# DIS08070H-V2_0-20231204.net
KiCad netlist of a schematic drawn in EAGLE
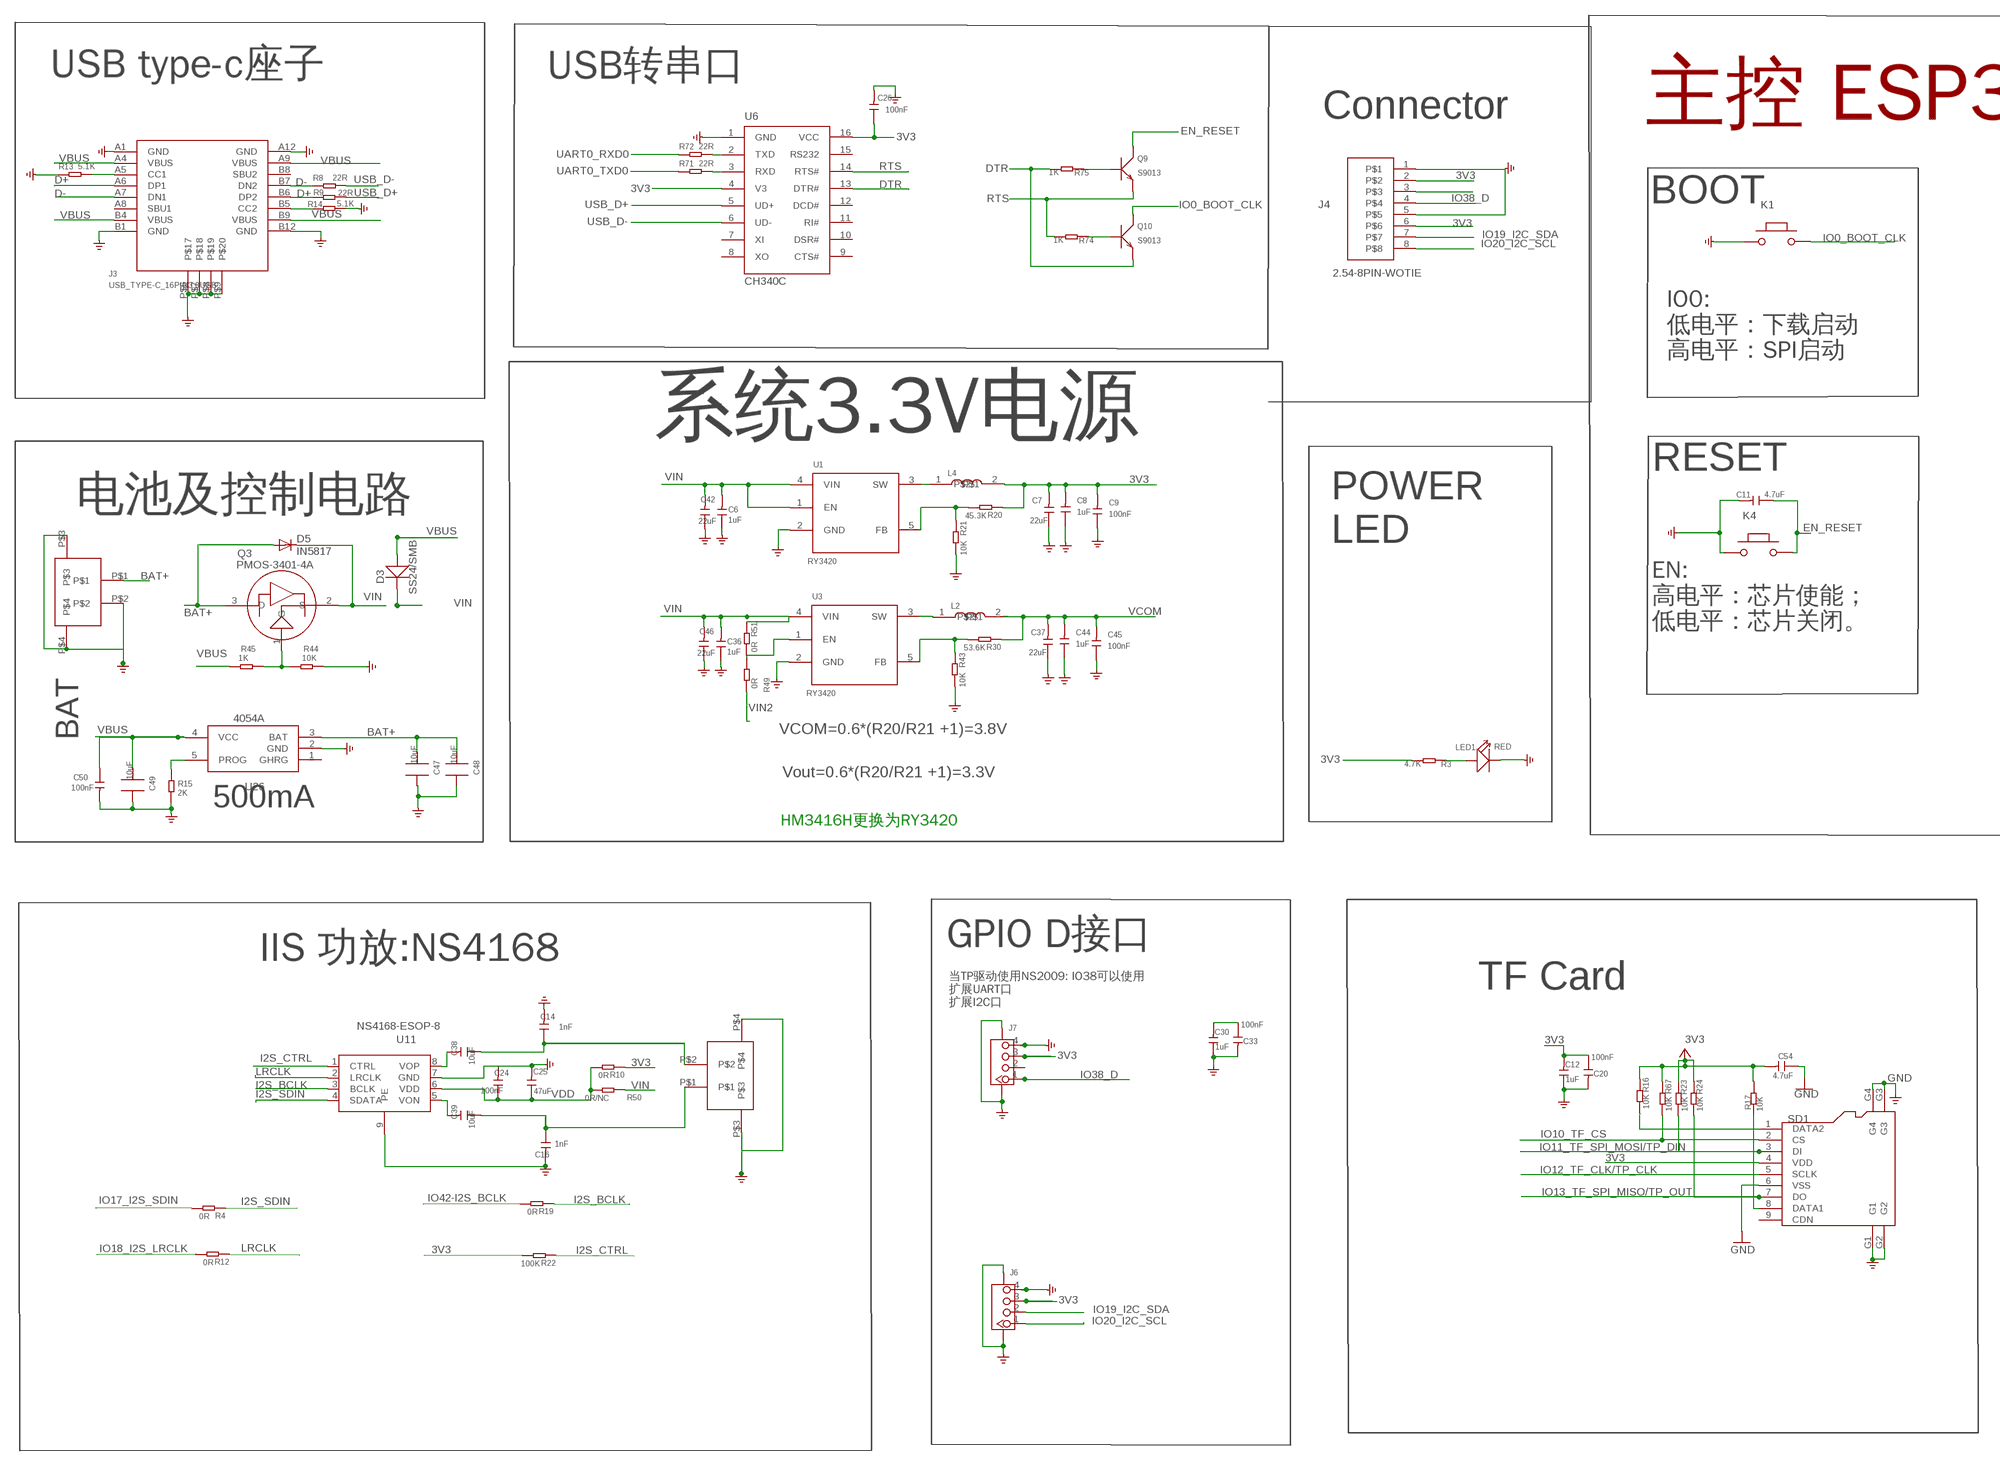
[diagram p0: schematic, sheet 1, part 1 of 2]
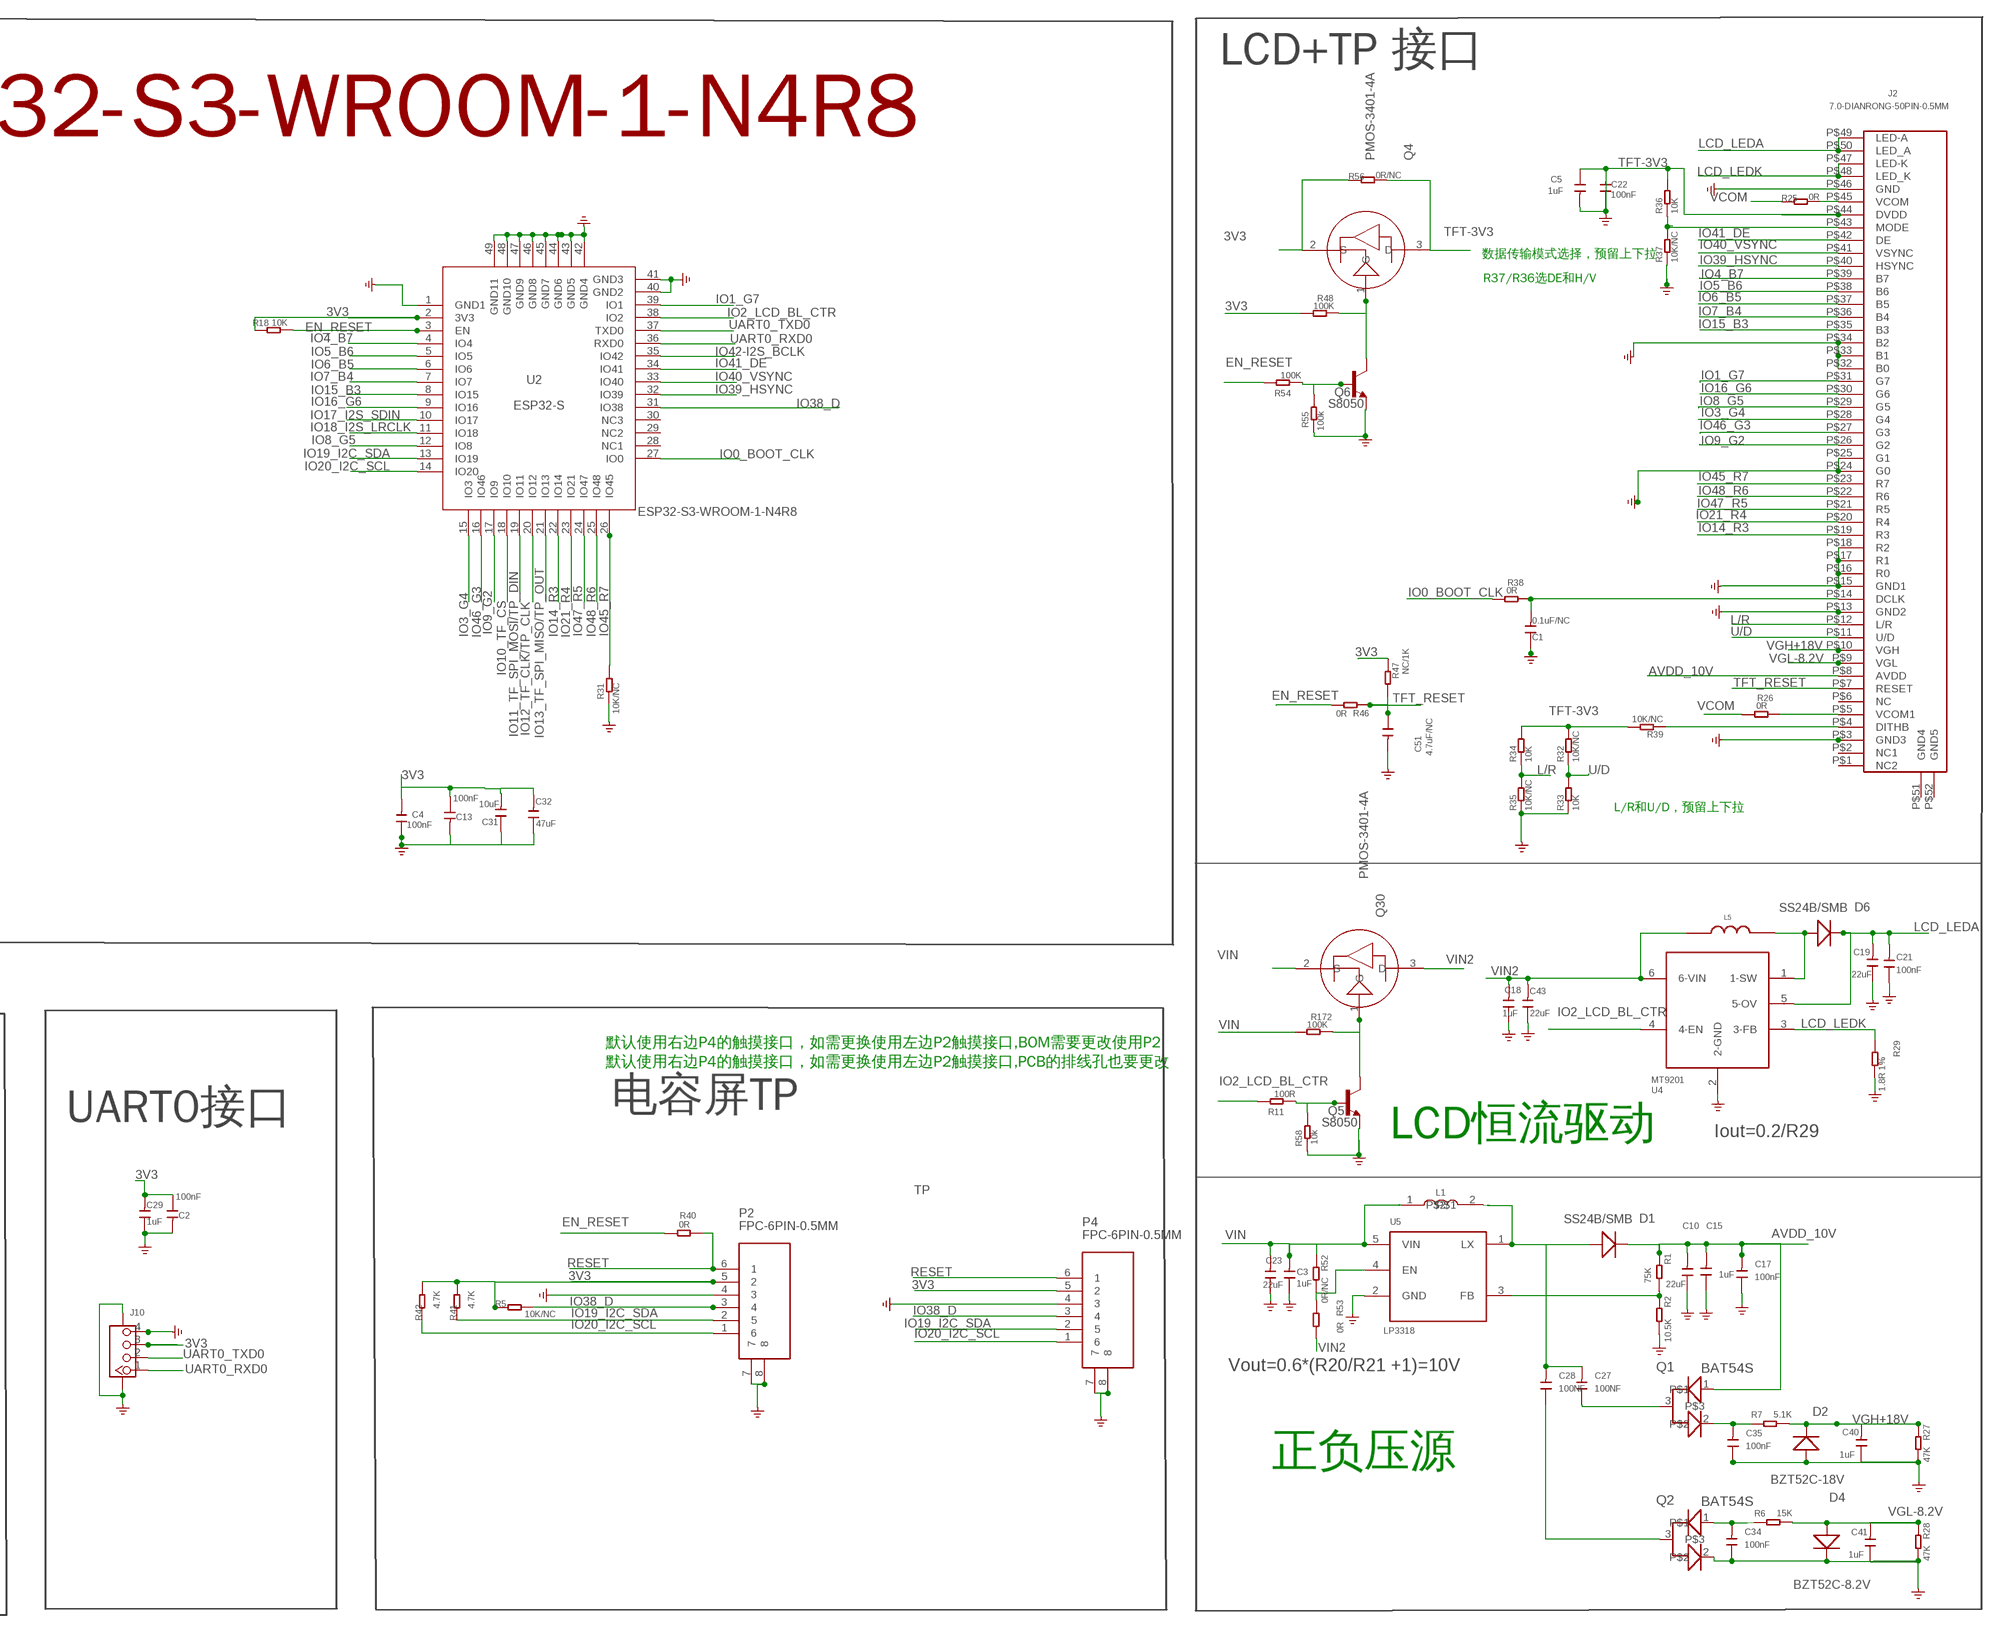
[diagram p1: schematic, sheet 1, part 2 of 2]

(export (version "E")
  (design (tool "Eeschema 10.0.6"))
  (components
    (comp (ref "C1")
      (value "0.1uF/NC")
      (footprint "eagle-import:DISCRETE_C0603")
      (libsource (lib "eagle-import") (part "DISCRETE_C-0603"))
    )
    (comp (ref "C2")
      (value "100nF")
      (footprint "eagle-import:C0603")
      (libsource (lib "eagle-import") (part "C-0603"))
    )
    (comp (ref "C3")
      (value "1uF")
      (footprint "eagle-import:0603")
      (libsource (lib "eagle-import") (part "C0603"))
    )
    (comp (ref "C4")
      (value "100nF")
      (footprint "eagle-import:C0603")
      (libsource (lib "eagle-import") (part "C-0603"))
    )
    (comp (ref "C5")
      (value "1uF")
      (footprint "eagle-import:C0603")
      (libsource (lib "eagle-import") (part "C-0603"))
    )
    (comp (ref "C6")
      (value "1uF")
      (footprint "eagle-import:0603")
      (libsource (lib "eagle-import") (part "C0603"))
    )
    (comp (ref "C7")
      (value "22uF")
      (footprint "eagle-import:0805")
      (libsource (lib "eagle-import") (part "C0805"))
    )
    (comp (ref "C8")
      (value "1uF")
      (footprint "eagle-import:0603")
      (libsource (lib "eagle-import") (part "C0603"))
    )
    (comp (ref "C9")
      (value "100nF")
      (footprint "eagle-import:0603")
      (libsource (lib "eagle-import") (part "C0603"))
    )
    (comp (ref "C10")
      (value "22uF")
      (footprint "eagle-import:0805")
      (libsource (lib "eagle-import") (part "C0805"))
    )
    (comp (ref "C11")
      (value "4.7uF")
      (footprint "eagle-import:0603")
      (libsource (lib "eagle-import") (part "C0603"))
    )
    (comp (ref "C12")
      (value "1uF")
      (footprint "eagle-import:DISCRETE_C0603")
      (libsource (lib "eagle-import") (part "A_xbj_DISCRETE_C-0603"))
    )
    (comp (ref "C13")
      (value "100nF")
      (footprint "eagle-import:C0603")
      (libsource (lib "eagle-import") (part "C-0603"))
    )
    (comp (ref "C14")
      (value "1nF")
      (footprint "eagle-import:C0603")
      (libsource (lib "eagle-import") (part "C-0603"))
    )
    (comp (ref "C15")
      (value "1uF")
      (footprint "eagle-import:0603")
      (libsource (lib "eagle-import") (part "C0603"))
    )
    (comp (ref "C16")
      (value "1nF")
      (footprint "eagle-import:C0603")
      (libsource (lib "eagle-import") (part "C-0603"))
    )
    (comp (ref "C17")
      (value "100nF")
      (footprint "eagle-import:0603")
      (libsource (lib "eagle-import") (part "C0603"))
    )
    (comp (ref "C18")
      (value "1uF")
      (footprint "eagle-import:0603")
      (libsource (lib "eagle-import") (part "C0603"))
    )
    (comp (ref "C19")
      (value "22uF")
      (footprint "eagle-import:0805")
      (libsource (lib "eagle-import") (part "C0805"))
    )
    (comp (ref "C20")
      (value "100nF")
      (footprint "eagle-import:C0603")
      (libsource (lib "eagle-import") (part "C-0603"))
    )
    (comp (ref "C21")
      (value "100nF")
      (footprint "eagle-import:0603")
      (libsource (lib "eagle-import") (part "C0603"))
    )
    (comp (ref "C22")
      (value "100nF")
      (footprint "eagle-import:C0603")
      (libsource (lib "eagle-import") (part "C-0603"))
    )
    (comp (ref "C23")
      (value "22uF")
      (footprint "eagle-import:0805")
      (libsource (lib "eagle-import") (part "C0805"))
    )
    (comp (ref "C24")
      (value "100nF")
      (footprint "eagle-import:C0603")
      (libsource (lib "eagle-import") (part "C-0603"))
    )
    (comp (ref "C25")
      (value "47uF")
      (footprint "eagle-import:0805")
      (libsource (lib "eagle-import") (part "C0805"))
    )
    (comp (ref "C26")
      (value "100nF")
      (footprint "eagle-import:0603")
      (libsource (lib "eagle-import") (part "C0603"))
    )
    (comp (ref "C27")
      (value "100NF")
      (footprint "eagle-import:0603")
      (libsource (lib "eagle-import") (part "C0603"))
    )
    (comp (ref "C28")
      (value "100NF")
      (footprint "eagle-import:0603")
      (libsource (lib "eagle-import") (part "C0603"))
    )
    (comp (ref "C29")
      (value "1uF")
      (footprint "eagle-import:DISCRETE_C0603")
      (libsource (lib "eagle-import") (part "A_xbj_DISCRETE_C-0603"))
    )
    (comp (ref "C30")
      (value "1uF")
      (footprint "eagle-import:DISCRETE_C0603")
      (libsource (lib "eagle-import") (part "A_xbj_DISCRETE_C-0603"))
    )
    (comp (ref "C31")
      (value "10uF")
      (footprint "eagle-import:DISCRETE_C0603")
      (libsource (lib "eagle-import") (part "DISCRETE_C-0603"))
    )
    (comp (ref "C32")
      (value "47uF")
      (footprint "eagle-import:0805")
      (libsource (lib "eagle-import") (part "C0805"))
    )
    (comp (ref "C33")
      (value "100nF")
      (footprint "eagle-import:C0603")
      (libsource (lib "eagle-import") (part "C-0603"))
    )
    (comp (ref "C34")
      (value "100nF")
      (footprint "eagle-import:0603")
      (libsource (lib "eagle-import") (part "C0603"))
    )
    (comp (ref "C35")
      (value "100nF")
      (footprint "eagle-import:0603")
      (libsource (lib "eagle-import") (part "C0603"))
    )
    (comp (ref "C36")
      (value "1uF")
      (footprint "eagle-import:0603")
      (libsource (lib "eagle-import") (part "C0603"))
    )
    (comp (ref "C37")
      (value "22uF")
      (footprint "eagle-import:0805")
      (libsource (lib "eagle-import") (part "C0805"))
    )
    (comp (ref "C38")
      (value "10uF")
      (footprint "eagle-import:C0603")
      (libsource (lib "eagle-import") (part "C-0603"))
    )
    (comp (ref "C39")
      (value "10uF")
      (footprint "eagle-import:C0603")
      (libsource (lib "eagle-import") (part "C-0603"))
    )
    (comp (ref "C40")
      (value "1uF")
      (footprint "eagle-import:0805")
      (libsource (lib "eagle-import") (part "C0805"))
    )
    (comp (ref "C41")
      (value "1uF")
      (footprint "eagle-import:0805")
      (libsource (lib "eagle-import") (part "C0805"))
    )
    (comp (ref "C42")
      (value "22uF")
      (footprint "eagle-import:0805")
      (libsource (lib "eagle-import") (part "C0805"))
    )
    (comp (ref "C43")
      (value "22uF")
      (footprint "eagle-import:0805")
      (libsource (lib "eagle-import") (part "C0805"))
    )
    (comp (ref "C44")
      (value "1uF")
      (footprint "eagle-import:0603")
      (libsource (lib "eagle-import") (part "C0603"))
    )
    (comp (ref "C45")
      (value "100nF")
      (footprint "eagle-import:0603")
      (libsource (lib "eagle-import") (part "C0603"))
    )
    (comp (ref "C46")
      (value "22uF")
      (footprint "eagle-import:0805")
      (libsource (lib "eagle-import") (part "C0805"))
    )
    (comp (ref "C47")
      (value "10uF")
      (footprint "eagle-import:0805_S")
      (libsource (lib "eagle-import") (part "C0805_S"))
    )
    (comp (ref "C48")
      (value "10uF")
      (footprint "eagle-import:0805_S")
      (libsource (lib "eagle-import") (part "C0805_S"))
    )
    (comp (ref "C49")
      (value "10uF")
      (footprint "eagle-import:0805_S")
      (libsource (lib "eagle-import") (part "C0805_S"))
    )
    (comp (ref "C50")
      (value "100nF")
      (footprint "eagle-import:C0603")
      (libsource (lib "eagle-import") (part "C-0603"))
    )
    (comp (ref "C51")
      (value "4.7uF/NC")
      (footprint "eagle-import:0603")
      (libsource (lib "eagle-import") (part "C0603"))
    )
    (comp (ref "C54")
      (value "4.7uF")
      (footprint "eagle-import:DISCRETE_C0603")
      (libsource (lib "eagle-import") (part "DISCRETE_C-0603"))
    )
    (comp (ref "D1")
      (value "SS24B/SMB")
      (footprint "eagle-import:214AB")
      (libsource (lib "eagle-import") (part "214ABDO-214AB"))
    )
    (comp (ref "D2")
      (value "BZT52C-18V")
      (footprint "eagle-import:DISCRETE_SOD123")
      (libsource (lib "eagle-import") (part "DISCRETE_D1206"))
    )
    (comp (ref "D3")
      (value "SS24/SMB")
      (footprint "eagle-import:214AB")
      (libsource (lib "eagle-import") (part "214ABDO-214AB"))
    )
    (comp (ref "D4")
      (value "BZT52C-8.2V")
      (footprint "eagle-import:DISCRETE_SOD123")
      (libsource (lib "eagle-import") (part "DISCRETE_D1206"))
    )
    (comp (ref "D5")
      (value "IN5817")
      (footprint "eagle-import:DO-214AC")
      (libsource (lib "eagle-import") (part "DIODE-DO-214AC"))
    )
    (comp (ref "D6")
      (value "SS24B/SMB")
      (footprint "eagle-import:214AB")
      (libsource (lib "eagle-import") (part "214ABDO-214AB"))
    )
    (comp (ref "J1")
      (value "PH2.0WT-2PIN")
      (footprint "eagle-import:PH2.0WT-2PIN")
      (libsource (lib "eagle-import") (part "PH2.0WT-2PIN"))
    )
    (comp (ref "J2")
      (value "7.0-DIANRONG-50PIN-0.5MM")
      (footprint "eagle-import:7.0-DAINRONG-50PIN-0.5MM")
      (libsource (lib "eagle-import") (part "7.0-DIANRONG-50PIN-0.5MM"))
    )
    (comp (ref "J3")
      (value "USB_TYPE-C_16PIN3.0USB")
      (footprint "eagle-import:KEVIN_3.0TYPEC-SMD")
      (libsource (lib "eagle-import") (part "USB_TYPE-C_16PIN3.0USB"))
    )
    (comp (ref "J4")
      (value "2.54-8PIN-WOTIE")
      (footprint "eagle-import:2.54-8P-WOTIE")
      (libsource (lib "eagle-import") (part "2.54-8PIN-WOTIE"))
    )
    (comp (ref "J5")
      (value "PH2.0WT-2PIN")
      (footprint "eagle-import:PH2.0WT-2PIN")
      (libsource (lib "eagle-import") (part "PH2.0WT-2PIN"))
    )
    (comp (ref "J6")
      (value "CONNECTOR_TWIG-4P-2.0-SMD-FEMALE-REINFORCE90D")
      (footprint "eagle-import:CONNECTOR_4P-SMD-2.0-90D")
      (libsource (lib "eagle-import") (part "CONNECTOR_TWIG-4P-2.0-SMD-FEMALE-REINFORCE90D"))
    )
    (comp (ref "J7")
      (value "CONNECTOR_TWIG-4P-2.0-SMD-FEMALE-REINFORCE90D")
      (footprint "eagle-import:CONNECTOR_4P-SMD-2.0-90D")
      (libsource (lib "eagle-import") (part "CONNECTOR_TWIG-4P-2.0-SMD-FEMALE-REINFORCE90D"))
    )
    (comp (ref "J10")
      (value "CONNECTOR_TWIG-4P-2.0-SMD-FEMALE-REINFORCE90D")
      (footprint "eagle-import:CONNECTOR_4P-SMD-2.0-90D")
      (libsource (lib "eagle-import") (part "CONNECTOR_TWIG-4P-2.0-SMD-FEMALE-REINFORCE90D"))
    )
    (comp (ref "K1")
      (value "BUTTON")
      (footprint "eagle-import:157SW")
      (libsource (lib "eagle-import") (part "PB157"))
    )
    (comp (ref "K4")
      (value "BUTTON")
      (footprint "eagle-import:157SW")
      (libsource (lib "eagle-import") (part "PB157"))
    )
    (comp (ref "L1")
      (value "L-0530")
      (footprint "eagle-import:CD54_CD54")
      (libsource (lib "eagle-import") (part "L-0530"))
    )
    (comp (ref "L2")
      (value "L-0530")
      (footprint "eagle-import:CD54_CD54")
      (libsource (lib "eagle-import") (part "L-0530"))
    )
    (comp (ref "L4")
      (value "L-0530")
      (footprint "eagle-import:CD54_CD54")
      (libsource (lib "eagle-import") (part "L-0530"))
    )
    (comp (ref "L5")
      (value "CD32_6.8uH")
      (footprint "eagle-import:CD32")
      (libsource (lib "eagle-import") (part "CD32_950MA"))
    )
    (comp (ref "LED1")
      (value "RED")
      (footprint "eagle-import:DISCRETE_LED-0603")
      (libsource (lib "eagle-import") (part "DISCRETE_LED0603"))
    )
    (comp (ref "P2")
      (value "FPC-6PIN-0.5MM")
      (footprint "eagle-import:FPC-6PIN-0.5MM")
      (libsource (lib "eagle-import") (part "FPC-6PIN-0.5MM"))
    )
    (comp (ref "P4")
      (value "FPC-6PIN-0.5MM")
      (footprint "eagle-import:FPC-6PIN-0.5MM")
      (libsource (lib "eagle-import") (part "FPC-6PIN-0.5MM"))
    )
    (comp (ref "Q1")
      (value "BAT54S")
      (footprint "eagle-import:SOT23-3")
      (libsource (lib "eagle-import") (part "BAT54S"))
    )
    (comp (ref "Q2")
      (value "BAT54S")
      (footprint "eagle-import:SOT23-3")
      (libsource (lib "eagle-import") (part "BAT54S"))
    )
    (comp (ref "Q3")
      (value "PMOS-3401-4A")
      (footprint "eagle-import:SOT-23")
      (libsource (lib "eagle-import") (part "P-MOS-SOT23"))
    )
    (comp (ref "Q4")
      (value "PMOS-3401-4A")
      (footprint "eagle-import:SOT-23")
      (libsource (lib "eagle-import") (part "P-MOS-SOT23"))
    )
    (comp (ref "Q5")
      (value "S8050")
      (footprint "eagle-import:SPARKFUN_SOT23")
      (libsource (lib "eagle-import") (part "SPARKFUN_TRANSISTOR_NPNSOT23"))
    )
    (comp (ref "Q6")
      (value "S8050")
      (footprint "eagle-import:SPARKFUN_SOT23")
      (libsource (lib "eagle-import") (part "SPARKFUN_TRANSISTOR_NPNSOT23"))
    )
    (comp (ref "Q9")
      (value "S9013")
      (footprint "eagle-import:SOT23@1")
      (libsource (lib "eagle-import") (part "TRANSISTOR-NPN-SOT23"))
    )
    (comp (ref "Q10")
      (value "S9013")
      (footprint "eagle-import:SOT23@1")
      (libsource (lib "eagle-import") (part "TRANSISTOR-NPN-SOT23"))
    )
    (comp (ref "Q30")
      (value "PMOS-3401-4A")
      (footprint "eagle-import:SOT-23")
      (libsource (lib "eagle-import") (part "P-MOS-SOT23"))
    )
    (comp (ref "R1")
      (value "75K")
      (footprint "eagle-import:DISCRETE_R0603")
      (libsource (lib "eagle-import") (part "Crowtail-_LED-V2.0-20190615-01_DISCRETE_R-0603"))
    )
    (comp (ref "R2")
      (value "10.5K")
      (footprint "eagle-import:DISCRETE_R0603")
      (libsource (lib "eagle-import") (part "Crowtail-_LED-V2.0-20190615-01_DISCRETE_R-0603"))
    )
    (comp (ref "R3")
      (value "4.7K")
      (footprint "eagle-import:DISCRETE_R0603")
      (libsource (lib "eagle-import") (part "Crowtail-_LED-V2.0-20190615-01_DISCRETE_R-0603"))
    )
    (comp (ref "R4")
      (value "0R")
      (footprint "eagle-import:DISCRETE_R0603")
      (libsource (lib "eagle-import") (part "Crowtail-_LED-V2.0-20190615-01_DISCRETE_R-0603"))
    )
    (comp (ref "R5")
      (value "10K/NC")
      (footprint "eagle-import:DISCRETE_R0603")
      (libsource (lib "eagle-import") (part "Crowtail-_LED-V2.0-20190615-01_DISCRETE_R-0603"))
    )
    (comp (ref "R6")
      (value "15K")
      (footprint "eagle-import:DISCRETE_R0603")
      (libsource (lib "eagle-import") (part "Crowtail-_LED-V2.0-20190615-01_DISCRETE_R-0603"))
    )
    (comp (ref "R7")
      (value "5.1K")
      (footprint "eagle-import:DISCRETE_R0603")
      (libsource (lib "eagle-import") (part "Crowtail-_LED-V2.0-20190615-01_DISCRETE_R-0603"))
    )
    (comp (ref "R8")
      (value "22R")
      (footprint "eagle-import:DISCRETE_R0603")
      (libsource (lib "eagle-import") (part "Crowtail-_LED-V2.0-20190615-01_DISCRETE_R-0603"))
    )
    (comp (ref "R9")
      (value "22R")
      (footprint "eagle-import:DISCRETE_R0603")
      (libsource (lib "eagle-import") (part "Crowtail-_LED-V2.0-20190615-01_DISCRETE_R-0603"))
    )
    (comp (ref "R10")
      (value "0R")
      (footprint "eagle-import:DISCRETE_R0603")
      (libsource (lib "eagle-import") (part "Crowtail-_LED-V2.0-20190615-01_DISCRETE_R-0603"))
    )
    (comp (ref "R11")
      (value "100R")
      (footprint "eagle-import:R0603")
      (libsource (lib "eagle-import") (part "R0603"))
    )
    (comp (ref "R12")
      (value "0R")
      (footprint "eagle-import:DISCRETE_R0603")
      (libsource (lib "eagle-import") (part "Crowtail-_LED-V2.0-20190615-01_DISCRETE_R-0603"))
    )
    (comp (ref "R13")
      (value "5.1K")
      (footprint "eagle-import:DISCRETE_R0603")
      (libsource (lib "eagle-import") (part "Crowtail-_LED-V2.0-20190615-01_DISCRETE_R-0603"))
    )
    (comp (ref "R14")
      (value "5.1K")
      (footprint "eagle-import:DISCRETE_R0603")
      (libsource (lib "eagle-import") (part "Crowtail-_LED-V2.0-20190615-01_DISCRETE_R-0603"))
    )
    (comp (ref "R15")
      (value "2K")
      (footprint "eagle-import:DISCRETE_R0603")
      (libsource (lib "eagle-import") (part "DISCRETE_R-0603"))
    )
    (comp (ref "R16")
      (value "10K")
      (footprint "eagle-import:DISCRETE_R0603")
      (libsource (lib "eagle-import") (part "Crowtail-_LED-V2.0-20190615-01_DISCRETE_R-0603"))
    )
    (comp (ref "R17")
      (value "10K")
      (footprint "eagle-import:DISCRETE_R0603")
      (libsource (lib "eagle-import") (part "Crowtail-_LED-V2.0-20190615-01_DISCRETE_R-0603"))
    )
    (comp (ref "R18")
      (value "10K")
      (footprint "eagle-import:DISCRETE_R0603")
      (libsource (lib "eagle-import") (part "Crowtail-_LED-V2.0-20190615-01_DISCRETE_R-0603"))
    )
    (comp (ref "R19")
      (value "0R")
      (footprint "eagle-import:DISCRETE_R0603")
      (libsource (lib "eagle-import") (part "Crowtail-_LED-V2.0-20190615-01_DISCRETE_R-0603"))
    )
    (comp (ref "R20")
      (value "45.3K")
      (footprint "eagle-import:DISCRETE_R0603")
      (libsource (lib "eagle-import") (part "Crowtail-_LED-V2.0-20190615-01_DISCRETE_R-0603"))
    )
    (comp (ref "R21")
      (value "10K")
      (footprint "eagle-import:DISCRETE_R0603")
      (libsource (lib "eagle-import") (part "Crowtail-_LED-V2.0-20190615-01_DISCRETE_R-0603"))
    )
    (comp (ref "R22")
      (value "100K")
      (footprint "eagle-import:DISCRETE_R0603")
      (libsource (lib "eagle-import") (part "Crowtail-_LED-V2.0-20190615-01_DISCRETE_R-0603"))
    )
    (comp (ref "R23")
      (value "10K")
      (footprint "eagle-import:DISCRETE_R0603")
      (libsource (lib "eagle-import") (part "Crowtail-_LED-V2.0-20190615-01_DISCRETE_R-0603"))
    )
    (comp (ref "R24")
      (value "10K")
      (footprint "eagle-import:DISCRETE_R0603")
      (libsource (lib "eagle-import") (part "Crowtail-_LED-V2.0-20190615-01_DISCRETE_R-0603"))
    )
    (comp (ref "R25")
      (value "0R")
      (footprint "eagle-import:DISCRETE_R0603")
      (libsource (lib "eagle-import") (part "Crowtail-_LED-V2.0-20190615-01_DISCRETE_R-0603"))
    )
    (comp (ref "R26")
      (value "0R")
      (footprint "eagle-import:R0603")
      (libsource (lib "eagle-import") (part "R-0603"))
    )
    (comp (ref "R27")
      (value "47K")
      (footprint "eagle-import:DISCRETE_R0603")
      (libsource (lib "eagle-import") (part "Crowtail-_LED-V2.0-20190615-01_DISCRETE_R-0603"))
    )
    (comp (ref "R28")
      (value "47K")
      (footprint "eagle-import:DISCRETE_R0603")
      (libsource (lib "eagle-import") (part "Crowtail-_LED-V2.0-20190615-01_DISCRETE_R-0603"))
    )
    (comp (ref "R29")
      (value "1.8R 1%")
      (footprint "eagle-import:DISCRETE_R0603")
      (libsource (lib "eagle-import") (part "Crowtail-_LED-V2.0-20190615-01_DISCRETE_R-0603"))
    )
    (comp (ref "R30")
      (value "53.6K")
      (footprint "eagle-import:DISCRETE_R0603")
      (libsource (lib "eagle-import") (part "Crowtail-_LED-V2.0-20190615-01_DISCRETE_R-0603"))
    )
    (comp (ref "R31")
      (value "10K/NC")
      (footprint "eagle-import:R0603")
      (libsource (lib "eagle-import") (part "R0603"))
    )
    (comp (ref "R32")
      (value "10K/NC")
      (footprint "eagle-import:DISCRETE_R0603")
      (libsource (lib "eagle-import") (part "DISCRETE_R-0603"))
    )
    (comp (ref "R33")
      (value "10K")
      (footprint "eagle-import:DISCRETE_R0603")
      (libsource (lib "eagle-import") (part "DISCRETE_R-0603"))
    )
    (comp (ref "R34")
      (value "10K")
      (footprint "eagle-import:DISCRETE_R0603")
      (libsource (lib "eagle-import") (part "DISCRETE_R-0603"))
    )
    (comp (ref "R35")
      (value "10K/NC")
      (footprint "eagle-import:DISCRETE_R0603")
      (libsource (lib "eagle-import") (part "DISCRETE_R-0603"))
    )
    (comp (ref "R36")
      (value "10K")
      (footprint "eagle-import:DISCRETE_R0603")
      (libsource (lib "eagle-import") (part "DISCRETE_R-0603"))
    )
    (comp (ref "R37")
      (value "10K/NC")
      (footprint "eagle-import:DISCRETE_R0603")
      (libsource (lib "eagle-import") (part "DISCRETE_R-0603"))
    )
    (comp (ref "R38")
      (value "0R")
      (footprint "eagle-import:R0603")
      (libsource (lib "eagle-import") (part "R-0603"))
    )
    (comp (ref "R39")
      (value "10K/NC")
      (footprint "eagle-import:DISCRETE_R0603")
      (libsource (lib "eagle-import") (part "DISCRETE_R-0603"))
    )
    (comp (ref "R40")
      (value "0R")
      (footprint "eagle-import:R0603")
      (libsource (lib "eagle-import") (part "R-0603"))
    )
    (comp (ref "R41")
      (value "4.7K")
      (footprint "eagle-import:DISCRETE_R0603")
      (libsource (lib "eagle-import") (part "Crowtail-_LED-V2.0-20190615-01_DISCRETE_R-0603"))
    )
    (comp (ref "R42")
      (value "4.7K")
      (footprint "eagle-import:DISCRETE_R0603")
      (libsource (lib "eagle-import") (part "Crowtail-_LED-V2.0-20190615-01_DISCRETE_R-0603"))
    )
    (comp (ref "R43")
      (value "10K")
      (footprint "eagle-import:DISCRETE_R0603")
      (libsource (lib "eagle-import") (part "Crowtail-_LED-V2.0-20190615-01_DISCRETE_R-0603"))
    )
    (comp (ref "R44")
      (value "10K")
      (footprint "eagle-import:DISCRETE_R0603")
      (libsource (lib "eagle-import") (part "DISCRETE_R-0603"))
    )
    (comp (ref "R45")
      (value "1K")
      (footprint "eagle-import:DISCRETE_R0603")
      (libsource (lib "eagle-import") (part "DISCRETE_R-0603"))
    )
    (comp (ref "R46")
      (value "0R")
      (footprint "eagle-import:DISCRETE_R0603")
      (libsource (lib "eagle-import") (part "Crowtail-_LED-V2.0-20190615-01_DISCRETE_R-0603"))
    )
    (comp (ref "R47")
      (value "NC/1K")
      (footprint "eagle-import:DISCRETE_R0603")
      (libsource (lib "eagle-import") (part "Crowtail-_LED-V2.0-20190615-01_DISCRETE_R-0603"))
    )
    (comp (ref "R48")
      (value "100K")
      (footprint "eagle-import:R0603")
      (libsource (lib "eagle-import") (part "R-0603"))
    )
    (comp (ref "R49")
      (value "0R")
      (footprint "eagle-import:DISCRETE_R0603")
      (libsource (lib "eagle-import") (part "Crowtail-_LED-V2.0-20190615-01_DISCRETE_R-0603"))
    )
    (comp (ref "R50")
      (value "0R/NC")
      (footprint "eagle-import:DISCRETE_R0603")
      (libsource (lib "eagle-import") (part "Crowtail-_LED-V2.0-20190615-01_DISCRETE_R-0603"))
    )
    (comp (ref "R51")
      (value "0R")
      (footprint "eagle-import:DISCRETE_R0603")
      (libsource (lib "eagle-import") (part "Crowtail-_LED-V2.0-20190615-01_DISCRETE_R-0603"))
    )
    (comp (ref "R52")
      (value "0R/NC")
      (footprint "eagle-import:DISCRETE_R0603")
      (libsource (lib "eagle-import") (part "Crowtail-_LED-V2.0-20190615-01_DISCRETE_R-0603"))
    )
    (comp (ref "R53")
      (value "0R")
      (footprint "eagle-import:DISCRETE_R0603")
      (libsource (lib "eagle-import") (part "Crowtail-_LED-V2.0-20190615-01_DISCRETE_R-0603"))
    )
    (comp (ref "R54")
      (value "100K")
      (footprint "eagle-import:R0603")
      (libsource (lib "eagle-import") (part "R0603"))
    )
    (comp (ref "R55")
      (value "100k")
      (footprint "eagle-import:R0603")
      (libsource (lib "eagle-import") (part "R0603"))
    )
    (comp (ref "R56")
      (value "0R/NC")
      (footprint "eagle-import:DISCRETE_R0603")
      (libsource (lib "eagle-import") (part "Crowtail-_LED-V2.0-20190615-01_DISCRETE_R-0603"))
    )
    (comp (ref "R58")
      (value "10k")
      (footprint "eagle-import:R0603")
      (libsource (lib "eagle-import") (part "R0603"))
    )
    (comp (ref "R67")
      (value "10K")
      (footprint "eagle-import:DISCRETE_R0603")
      (libsource (lib "eagle-import") (part "Crowtail-_LED-V2.0-20190615-01_DISCRETE_R-0603"))
    )
    (comp (ref "R71")
      (value "22R")
      (footprint "eagle-import:DISCRETE_R0603")
      (libsource (lib "eagle-import") (part "Crowtail-_LED-V2.0-20190615-01_DISCRETE_R-0603"))
    )
    (comp (ref "R72")
      (value "22R")
      (footprint "eagle-import:DISCRETE_R0603")
      (libsource (lib "eagle-import") (part "Crowtail-_LED-V2.0-20190615-01_DISCRETE_R-0603"))
    )
    (comp (ref "R74")
      (value "1K")
      (footprint "eagle-import:DISCRETE_R0603")
      (libsource (lib "eagle-import") (part "Crowtail-_LED-V2.0-20190615-01_DISCRETE_R-0603"))
    )
    (comp (ref "R75")
      (value "1K")
      (footprint "eagle-import:DISCRETE_R0603")
      (libsource (lib "eagle-import") (part "Crowtail-_LED-V2.0-20190615-01_DISCRETE_R-0603"))
    )
    (comp (ref "R172")
      (value "100K")
      (footprint "eagle-import:R0603")
      (libsource (lib "eagle-import") (part "R-0603"))
    )
    (comp (ref "SD1")
      (value "HOLDER-MICROSD-9P")
      (footprint "eagle-import:9P-SMD-W_-RING")
      (libsource (lib "eagle-import") (part "HOLDER-MICROSD-9P"))
    )
    (comp (ref "U1")
      (value "RY3420")
      (footprint "eagle-import:A_XBJ_SOT23-5")
      (libsource (lib "eagle-import") (part "A_XBJ_HM3420B"))
    )
    (comp (ref "U2")
      (value "ESP32-S")
      (footprint "eagle-import:ESP32-S3")
      (fields (field (name "U2") "ESP32-S3-WROOM-1-N4R8"))
      (libsource (lib "eagle-import") (part "ESP32-S"))
    )
    (comp (ref "U3")
      (value "RY3420")
      (footprint "eagle-import:A_XBJ_SOT23-5")
      (libsource (lib "eagle-import") (part "A_XBJ_HM3420B"))
    )
    (comp (ref "U4")
      (value "MT9201")
      (footprint "eagle-import:SOT23-6")
      (libsource (lib "eagle-import") (part "MT9201"))
    )
    (comp (ref "U5")
      (value "LP3318")
      (footprint "eagle-import:LP3318_SOT23-5")
      (libsource (lib "eagle-import") (part "LP3318"))
    )
    (comp (ref "U6")
      (value "CH340C")
      (footprint "eagle-import:SOP-16")
      (libsource (lib "eagle-import") (part "CH340G"))
    )
    (comp (ref "U11")
      (value "NS4168-ESOP-8")
      (footprint "eagle-import:NS4168-ESOP-8")
      (libsource (lib "eagle-import") (part "NS4168-ESOP-8"))
    )
    (comp (ref "U26")
      (value "4054A")
      (footprint "eagle-import:SOP23-5")
      (libsource (lib "eagle-import") (part "4054A"))
    )
  )
  (nets
    (net (code "1") (name "+3V3") (class "Default")
      (node (ref "C12") (pin "2") (pinfunction "2_2") (pintype "passive"))
      (node (ref "C13") (pin "1") (pinfunction "1_1") (pintype "passive"))
      (node (ref "C2") (pin "1") (pinfunction "1_1") (pintype "passive"))
      (node (ref "C20") (pin "1") (pinfunction "1_1") (pintype "passive"))
      (node (ref "C26") (pin "1") (pinfunction "1_1") (pintype "passive"))
      (node (ref "C29") (pin "2") (pinfunction "2_2") (pintype "passive"))
      (node (ref "C30") (pin "2") (pinfunction "2_2") (pintype "passive"))
      (node (ref "C31") (pin "2") (pinfunction "2_2") (pintype "passive"))
      (node (ref "C32") (pin "2") (pinfunction "2_2") (pintype "passive"))
      (node (ref "C33") (pin "1") (pinfunction "1_1") (pintype "passive"))
      (node (ref "C4") (pin "2") (pinfunction "2_2") (pintype "passive"))
      (node (ref "C54") (pin "2") (pinfunction "2_2") (pintype "passive"))
      (node (ref "C7") (pin "2") (pinfunction "2_2") (pintype "passive"))
      (node (ref "C8") (pin "2") (pinfunction "2_2") (pintype "passive"))
      (node (ref "C9") (pin "2") (pinfunction "2_2") (pintype "passive"))
      (node (ref "J10") (pin "3") (pinfunction "3_3") (pintype "bidirectional"))
      (node (ref "J4") (pin "2") (pinfunction "P$2_2") (pintype "bidirectional"))
      (node (ref "J4") (pin "6") (pinfunction "P$6_6") (pintype "bidirectional"))
      (node (ref "J6") (pin "3") (pinfunction "3_3") (pintype "bidirectional"))
      (node (ref "J7") (pin "3") (pinfunction "3_3") (pintype "bidirectional"))
      (node (ref "L4") (pin "2") (pinfunction "P$2_2") (pintype "bidirectional"))
      (node (ref "P2") (pin "5") (pinfunction "2_5") (pintype "bidirectional"))
      (node (ref "P4") (pin "5") (pinfunction "2_5") (pintype "bidirectional"))
      (node (ref "Q4") (pin "2") (pinfunction "S_2") (pintype "bidirectional"))
      (node (ref "R10") (pin "1") (pinfunction "1_1") (pintype "passive"))
      (node (ref "R16") (pin "1") (pinfunction "1_1") (pintype "passive"))
      (node (ref "R17") (pin "1") (pinfunction "1_1") (pintype "passive"))
      (node (ref "R18") (pin "1") (pinfunction "1_1") (pintype "passive"))
      (node (ref "R20") (pin "1") (pinfunction "1_1") (pintype "passive"))
      (node (ref "R22") (pin "2") (pinfunction "2_2") (pintype "passive"))
      (node (ref "R23") (pin "1") (pinfunction "1_1") (pintype "passive"))
      (node (ref "R24") (pin "1") (pinfunction "1_1") (pintype "passive"))
      (node (ref "R3") (pin "2") (pinfunction "2_2") (pintype "passive"))
      (node (ref "R41") (pin "2") (pinfunction "2_2") (pintype "passive"))
      (node (ref "R42") (pin "2") (pinfunction "2_2") (pintype "passive"))
      (node (ref "R47") (pin "2") (pinfunction "2_2") (pintype "passive"))
      (node (ref "R48") (pin "1") (pinfunction "1_1") (pintype "passive"))
      (node (ref "R5") (pin "1") (pinfunction "1_1") (pintype "passive"))
      (node (ref "R56") (pin "1") (pinfunction "1_1") (pintype "passive"))
      (node (ref "R67") (pin "1") (pinfunction "1_1") (pintype "passive"))
      (node (ref "SD1") (pin "4") (pinfunction "VDD_4") (pintype "bidirectional"))
      (node (ref "U2") (pin "2") (pinfunction "3V3_2") (pintype "bidirectional"))
      (node (ref "U6") (pin "16") (pinfunction "VCC_16") (pintype "bidirectional"))
      (node (ref "U6") (pin "4") (pinfunction "V3_4") (pintype "bidirectional"))
    )
    (net (code "2") (name "/AVDD_10V") (class "Default")
      (node (ref "C10") (pin "2") (pinfunction "2_2") (pintype "passive"))
      (node (ref "C15") (pin "2") (pinfunction "2_2") (pintype "passive"))
      (node (ref "C17") (pin "2") (pinfunction "2_2") (pintype "passive"))
      (node (ref "D1") (pin "2") (pinfunction "-_2") (pintype "passive"))
      (node (ref "J2") (pin "P$8") (pinfunction "AVDD_P$8") (pintype "bidirectional"))
      (node (ref "Q1") (pin "1") (pinfunction "P$1_1") (pintype "bidirectional"))
      (node (ref "R1") (pin "1") (pinfunction "1_1") (pintype "passive"))
    )
    (net (code "3") (name "/BAT+") (class "Default")
      (node (ref "C47") (pin "2") (pinfunction "2_2") (pintype "bidirectional"))
      (node (ref "C48") (pin "2") (pinfunction "2_2") (pintype "bidirectional"))
      (node (ref "D5") (pin "A") (pinfunction "A_A") (pintype "passive"))
      (node (ref "J1") (pin "P$1") (pinfunction "P$1_P$1") (pintype "bidirectional"))
      (node (ref "Q3") (pin "3") (pinfunction "D_3") (pintype "bidirectional"))
      (node (ref "U26") (pin "3") (pinfunction "BAT_3") (pintype "bidirectional"))
    )
    (net (code "4") (name "/D+") (class "Default")
      (node (ref "J3") (pin "A6") (pinfunction "DP1_A6") (pintype "bidirectional"))
      (node (ref "J3") (pin "B6") (pinfunction "DP2_B6") (pintype "bidirectional"))
      (node (ref "R9") (pin "1") (pinfunction "1_1") (pintype "passive"))
    )
    (net (code "5") (name "/D-") (class "Default")
      (node (ref "J3") (pin "A7") (pinfunction "DN1_A7") (pintype "bidirectional"))
      (node (ref "J3") (pin "B7") (pinfunction "DN2_B7") (pintype "bidirectional"))
      (node (ref "R8") (pin "1") (pinfunction "1_1") (pintype "passive"))
    )
    (net (code "6") (name "/DTR") (class "Default")
      (node (ref "Q10") (pin "2") (pinfunction "E_2") (pintype "passive"))
      (node (ref "R75") (pin "2") (pinfunction "2_2") (pintype "passive"))
      (node (ref "U6") (pin "13") (pinfunction "DTR#_13") (pintype "bidirectional"))
    )
    (net (code "7") (name "/EN_RESET") (class "Default")
      (node (ref "C11") (pin "1") (pinfunction "1_1") (pintype "passive"))
      (node (ref "K4") (pin "2") (pinfunction "2_2") (pintype "passive"))
      (node (ref "Q9") (pin "3") (pinfunction "C_3") (pintype "passive"))
      (node (ref "R18") (pin "2") (pinfunction "2_2") (pintype "passive"))
      (node (ref "R40") (pin "1") (pinfunction "1_1") (pintype "passive"))
      (node (ref "R46") (pin "2") (pinfunction "2_2") (pintype "passive"))
      (node (ref "R54") (pin "2") (pinfunction "2_2") (pintype "passive"))
      (node (ref "U2") (pin "3") (pinfunction "EN_3") (pintype "bidirectional"))
    )
    (net (code "8") (name "/I2S_BCLK") (class "Default")
      (node (ref "R19") (pin "1") (pinfunction "1_1") (pintype "passive"))
      (node (ref "U11") (pin "3") (pinfunction "BCLK_3") (pintype "bidirectional"))
    )
    (net (code "9") (name "/I2S_CTRL") (class "Default")
      (node (ref "R22") (pin "1") (pinfunction "1_1") (pintype "passive"))
      (node (ref "U11") (pin "1") (pinfunction "CTRL_1") (pintype "bidirectional"))
    )
    (net (code "10") (name "/I2S_SDIN") (class "Default")
      (node (ref "R4") (pin "1") (pinfunction "1_1") (pintype "passive"))
      (node (ref "U11") (pin "4") (pinfunction "SDATA_4") (pintype "bidirectional"))
    )
    (net (code "11") (name "/IO0_BOOT_CLK") (class "Default")
      (node (ref "K1") (pin "2") (pinfunction "2_2") (pintype "passive"))
      (node (ref "Q10") (pin "3") (pinfunction "C_3") (pintype "passive"))
      (node (ref "R38") (pin "1") (pinfunction "1_1") (pintype "passive"))
      (node (ref "U2") (pin "27") (pinfunction "IO0_27") (pintype "bidirectional"))
    )
    (net (code "12") (name "/IO1_G7") (class "Default")
      (node (ref "J2") (pin "P$31") (pinfunction "G7_P$31") (pintype "bidirectional"))
      (node (ref "U2") (pin "39") (pinfunction "IO1_39") (pintype "bidirectional"))
    )
    (net (code "13") (name "/IO2_LCD_BL_CTR") (class "Default")
      (node (ref "R11") (pin "2") (pinfunction "2_2") (pintype "passive"))
      (node (ref "U2") (pin "38") (pinfunction "IO2_38") (pintype "bidirectional"))
      (node (ref "U4") (pin "4") (pinfunction "4-EN_4") (pintype "bidirectional"))
    )
    (net (code "14") (name "/IO3_G4") (class "Default")
      (node (ref "J2") (pin "P$28") (pinfunction "G4_P$28") (pintype "bidirectional"))
      (node (ref "U2") (pin "15") (pinfunction "IO3_15") (pintype "bidirectional"))
    )
    (net (code "15") (name "/IO4_B7") (class "Default")
      (node (ref "J2") (pin "P$39") (pinfunction "B7_P$39") (pintype "bidirectional"))
      (node (ref "U2") (pin "4") (pinfunction "IO4_4") (pintype "bidirectional"))
    )
    (net (code "16") (name "/IO5_B6") (class "Default")
      (node (ref "J2") (pin "P$38") (pinfunction "B6_P$38") (pintype "bidirectional"))
      (node (ref "U2") (pin "5") (pinfunction "IO5_5") (pintype "bidirectional"))
    )
    (net (code "17") (name "/IO6_B5") (class "Default")
      (node (ref "J2") (pin "P$37") (pinfunction "B5_P$37") (pintype "bidirectional"))
      (node (ref "U2") (pin "6") (pinfunction "IO6_6") (pintype "bidirectional"))
    )
    (net (code "18") (name "/IO7_B4") (class "Default")
      (node (ref "J2") (pin "P$36") (pinfunction "B4_P$36") (pintype "bidirectional"))
      (node (ref "U2") (pin "7") (pinfunction "IO7_7") (pintype "bidirectional"))
    )
    (net (code "19") (name "/IO8_G5") (class "Default")
      (node (ref "J2") (pin "P$29") (pinfunction "G5_P$29") (pintype "bidirectional"))
      (node (ref "U2") (pin "12") (pinfunction "IO8_12") (pintype "bidirectional"))
    )
    (net (code "20") (name "/IO9_G2") (class "Default")
      (node (ref "J2") (pin "P$26") (pinfunction "G2_P$26") (pintype "bidirectional"))
      (node (ref "U2") (pin "17") (pinfunction "IO9_17") (pintype "bidirectional"))
    )
    (net (code "21") (name "/IO10_TF_CS") (class "Default")
      (node (ref "R67") (pin "2") (pinfunction "2_2") (pintype "passive"))
      (node (ref "SD1") (pin "2") (pinfunction "CS_2") (pintype "bidirectional"))
      (node (ref "U2") (pin "18") (pinfunction "IO10_18") (pintype "bidirectional"))
    )
    (net (code "22") (name "/IO11_TF_SPI_MOSI{slash}TP_DIN") (class "Default")
      (node (ref "R23") (pin "2") (pinfunction "2_2") (pintype "passive"))
      (node (ref "SD1") (pin "3") (pinfunction "DI_3") (pintype "bidirectional"))
      (node (ref "U2") (pin "19") (pinfunction "IO11_19") (pintype "bidirectional"))
    )
    (net (code "23") (name "/IO12_TF_CLK{slash}TP_CLK") (class "Default")
      (node (ref "SD1") (pin "5") (pinfunction "SCLK_5") (pintype "bidirectional"))
      (node (ref "U2") (pin "20") (pinfunction "IO12_20") (pintype "bidirectional"))
    )
    (net (code "24") (name "/IO13_TF_SPI_MISO{slash}TP_OUT") (class "Default")
      (node (ref "R24") (pin "2") (pinfunction "2_2") (pintype "passive"))
      (node (ref "SD1") (pin "7") (pinfunction "DO_7") (pintype "bidirectional"))
      (node (ref "U2") (pin "21") (pinfunction "IO13_21") (pintype "bidirectional"))
    )
    (net (code "25") (name "/IO14_R3") (class "Default")
      (node (ref "J2") (pin "P$19") (pinfunction "R3_P$19") (pintype "bidirectional"))
      (node (ref "U2") (pin "22") (pinfunction "IO14_22") (pintype "bidirectional"))
    )
    (net (code "26") (name "/IO15_B3") (class "Default")
      (node (ref "J2") (pin "P$35") (pinfunction "B3_P$35") (pintype "bidirectional"))
      (node (ref "U2") (pin "8") (pinfunction "IO15_8") (pintype "bidirectional"))
    )
    (net (code "27") (name "/IO16_G6") (class "Default")
      (node (ref "J2") (pin "P$30") (pinfunction "G6_P$30") (pintype "bidirectional"))
      (node (ref "U2") (pin "9") (pinfunction "IO16_9") (pintype "bidirectional"))
    )
    (net (code "28") (name "/IO17_I2S_SDIN") (class "Default")
      (node (ref "R4") (pin "2") (pinfunction "2_2") (pintype "passive"))
      (node (ref "U2") (pin "10") (pinfunction "IO17_10") (pintype "bidirectional"))
    )
    (net (code "29") (name "/IO18_I2S_LRCLK") (class "Default")
      (node (ref "R12") (pin "2") (pinfunction "2_2") (pintype "passive"))
      (node (ref "U2") (pin "11") (pinfunction "IO18_11") (pintype "bidirectional"))
    )
    (net (code "30") (name "/IO19_I2C_SDA") (class "Default")
      (node (ref "J4") (pin "7") (pinfunction "P$7_7") (pintype "bidirectional"))
      (node (ref "J6") (pin "2") (pinfunction "2_2") (pintype "bidirectional"))
      (node (ref "P2") (pin "2") (pinfunction "5_2") (pintype "bidirectional"))
      (node (ref "P4") (pin "2") (pinfunction "5_2") (pintype "bidirectional"))
      (node (ref "R41") (pin "1") (pinfunction "1_1") (pintype "passive"))
      (node (ref "U2") (pin "13") (pinfunction "IO19_13") (pintype "bidirectional"))
    )
    (net (code "31") (name "/IO20_I2C_SCL") (class "Default")
      (node (ref "J4") (pin "8") (pinfunction "P$8_8") (pintype "bidirectional"))
      (node (ref "J6") (pin "1") (pinfunction "1_1") (pintype "bidirectional"))
      (node (ref "P2") (pin "1") (pinfunction "6_1") (pintype "bidirectional"))
      (node (ref "P4") (pin "1") (pinfunction "6_1") (pintype "bidirectional"))
      (node (ref "R42") (pin "1") (pinfunction "1_1") (pintype "passive"))
      (node (ref "U2") (pin "14") (pinfunction "IO20_14") (pintype "bidirectional"))
    )
    (net (code "32") (name "/IO21_R4") (class "Default")
      (node (ref "J2") (pin "P$20") (pinfunction "R4_P$20") (pintype "bidirectional"))
      (node (ref "U2") (pin "23") (pinfunction "IO21_23") (pintype "bidirectional"))
    )
    (net (code "33") (name "/IO38_D") (class "Default")
      (node (ref "J4") (pin "4") (pinfunction "P$4_4") (pintype "bidirectional"))
      (node (ref "J7") (pin "1") (pinfunction "1_1") (pintype "bidirectional"))
      (node (ref "P2") (pin "3") (pinfunction "4_3") (pintype "bidirectional"))
      (node (ref "P4") (pin "3") (pinfunction "4_3") (pintype "bidirectional"))
      (node (ref "R5") (pin "2") (pinfunction "2_2") (pintype "passive"))
      (node (ref "U2") (pin "31") (pinfunction "IO38_31") (pintype "bidirectional"))
    )
    (net (code "34") (name "/IO39_HSYNC") (class "Default")
      (node (ref "J2") (pin "P$40") (pinfunction "HSYNC_P$40") (pintype "bidirectional"))
      (node (ref "U2") (pin "32") (pinfunction "IO39_32") (pintype "bidirectional"))
    )
    (net (code "35") (name "/IO40_VSYNC") (class "Default")
      (node (ref "J2") (pin "P$41") (pinfunction "VSYNC_P$41") (pintype "bidirectional"))
      (node (ref "U2") (pin "33") (pinfunction "IO40_33") (pintype "bidirectional"))
    )
    (net (code "36") (name "/IO41_DE") (class "Default")
      (node (ref "J2") (pin "P$42") (pinfunction "DE_P$42") (pintype "bidirectional"))
      (node (ref "U2") (pin "34") (pinfunction "IO41_34") (pintype "bidirectional"))
    )
    (net (code "37") (name "/IO42-I2S_BCLK") (class "Default")
      (node (ref "R19") (pin "2") (pinfunction "2_2") (pintype "passive"))
      (node (ref "U2") (pin "35") (pinfunction "IO42_35") (pintype "bidirectional"))
    )
    (net (code "38") (name "/IO45_R7") (class "Default")
      (node (ref "J2") (pin "P$23") (pinfunction "R7_P$23") (pintype "bidirectional"))
      (node (ref "R31") (pin "2") (pinfunction "2_2") (pintype "passive"))
      (node (ref "U2") (pin "26") (pinfunction "IO45_26") (pintype "bidirectional"))
    )
    (net (code "39") (name "/IO46_G3") (class "Default")
      (node (ref "J2") (pin "P$27") (pinfunction "G3_P$27") (pintype "bidirectional"))
      (node (ref "U2") (pin "16") (pinfunction "IO46_16") (pintype "bidirectional"))
    )
    (net (code "40") (name "/IO47_R5") (class "Default")
      (node (ref "J2") (pin "P$21") (pinfunction "R5_P$21") (pintype "bidirectional"))
      (node (ref "U2") (pin "24") (pinfunction "IO47_24") (pintype "bidirectional"))
    )
    (net (code "41") (name "/IO48_R6") (class "Default")
      (node (ref "J2") (pin "P$22") (pinfunction "R6_P$22") (pintype "bidirectional"))
      (node (ref "U2") (pin "25") (pinfunction "IO48_25") (pintype "bidirectional"))
    )
    (net (code "42") (name "/LCD_LEDA") (class "Default")
      (node (ref "C19") (pin "2") (pinfunction "2_2") (pintype "passive"))
      (node (ref "C21") (pin "2") (pinfunction "2_2") (pintype "passive"))
      (node (ref "D6") (pin "2") (pinfunction "-_2") (pintype "passive"))
      (node (ref "J2") (pin "P$49") (pinfunction "LED-A_P$49") (pintype "bidirectional"))
      (node (ref "J2") (pin "P$50") (pinfunction "LED_A_P$50") (pintype "bidirectional"))
      (node (ref "U4") (pin "5") (pinfunction "5-OV_5") (pintype "bidirectional"))
    )
    (net (code "43") (name "/LCD_LEDK") (class "Default")
      (node (ref "J2") (pin "P$47") (pinfunction "LED-K_P$47") (pintype "bidirectional"))
      (node (ref "J2") (pin "P$48") (pinfunction "LED_K_P$48") (pintype "bidirectional"))
      (node (ref "R29") (pin "1") (pinfunction "1_1") (pintype "passive"))
      (node (ref "U4") (pin "3") (pinfunction "3-FB_3") (pintype "bidirectional"))
    )
    (net (code "44") (name "/LRCLK") (class "Default")
      (node (ref "R12") (pin "1") (pinfunction "1_1") (pintype "passive"))
      (node (ref "U11") (pin "2") (pinfunction "LRCLK_2") (pintype "bidirectional"))
    )
    (net (code "45") (name "/L{slash}R") (class "Default")
      (node (ref "J2") (pin "P$12") (pinfunction "L/R_P$12") (pintype "bidirectional"))
      (node (ref "R34") (pin "1") (pinfunction "1_1") (pintype "passive"))
      (node (ref "R35") (pin "2") (pinfunction "2_2") (pintype "passive"))
    )
    (net (code "46") (name "/RESET") (class "Default")
      (node (ref "P2") (pin "6") (pinfunction "1_6") (pintype "bidirectional"))
      (node (ref "P4") (pin "6") (pinfunction "1_6") (pintype "bidirectional"))
      (node (ref "R40") (pin "2") (pinfunction "2_2") (pintype "passive"))
    )
    (net (code "47") (name "/RTS") (class "Default")
      (node (ref "Q9") (pin "2") (pinfunction "E_2") (pintype "passive"))
      (node (ref "R74") (pin "2") (pinfunction "2_2") (pintype "passive"))
      (node (ref "U6") (pin "14") (pinfunction "RTS#_14") (pintype "bidirectional"))
    )
    (net (code "48") (name "/TFT-3V3") (class "Default")
      (node (ref "C22") (pin "2") (pinfunction "2_2") (pintype "passive"))
      (node (ref "C5") (pin "1") (pinfunction "1_1") (pintype "passive"))
      (node (ref "J2") (pin "P$44") (pinfunction "DVDD_P$44") (pintype "bidirectional"))
      (node (ref "Q4") (pin "3") (pinfunction "D_3") (pintype "bidirectional"))
      (node (ref "R32") (pin "2") (pinfunction "2_2") (pintype "passive"))
      (node (ref "R34") (pin "2") (pinfunction "2_2") (pintype "passive"))
      (node (ref "R36") (pin "2") (pinfunction "2_2") (pintype "passive"))
      (node (ref "R39") (pin "2") (pinfunction "2_2") (pintype "passive"))
      (node (ref "R56") (pin "2") (pinfunction "2_2") (pintype "passive"))
    )
    (net (code "49") (name "/TFT_RESET") (class "Default")
      (node (ref "C51") (pin "1") (pinfunction "1_1") (pintype "passive"))
      (node (ref "J2") (pin "P$7") (pinfunction "RESET_P$7") (pintype "bidirectional"))
      (node (ref "R46") (pin "1") (pinfunction "1_1") (pintype "passive"))
      (node (ref "R47") (pin "1") (pinfunction "1_1") (pintype "passive"))
    )
    (net (code "50") (name "/UART0_RXD0") (class "Default")
      (node (ref "J10") (pin "1") (pinfunction "1_1") (pintype "bidirectional"))
      (node (ref "R72") (pin "1") (pinfunction "1_1") (pintype "passive"))
      (node (ref "U2") (pin "36") (pinfunction "RXD0_36") (pintype "bidirectional"))
    )
    (net (code "51") (name "/UART0_TXD0") (class "Default")
      (node (ref "J10") (pin "2") (pinfunction "2_2") (pintype "bidirectional"))
      (node (ref "R71") (pin "1") (pinfunction "1_1") (pintype "passive"))
      (node (ref "U2") (pin "37") (pinfunction "TXD0_37") (pintype "bidirectional"))
    )
    (net (code "52") (name "/USB_D+") (class "Default")
      (node (ref "R9") (pin "2") (pinfunction "2_2") (pintype "passive"))
      (node (ref "U6") (pin "5") (pinfunction "UD+_5") (pintype "bidirectional"))
    )
    (net (code "53") (name "/USB_D-") (class "Default")
      (node (ref "R8") (pin "2") (pinfunction "2_2") (pintype "passive"))
      (node (ref "U6") (pin "6") (pinfunction "UD-_6") (pintype "bidirectional"))
    )
    (net (code "54") (name "/U{slash}D") (class "Default")
      (node (ref "J2") (pin "P$11") (pinfunction "U/D_P$11") (pintype "bidirectional"))
      (node (ref "R32") (pin "1") (pinfunction "1_1") (pintype "passive"))
      (node (ref "R33") (pin "2") (pinfunction "2_2") (pintype "passive"))
    )
    (net (code "55") (name "/VBUS") (class "Default")
      (node (ref "C49") (pin "2") (pinfunction "2_2") (pintype "bidirectional"))
      (node (ref "C50") (pin "1") (pinfunction "1_1") (pintype "passive"))
      (node (ref "D3") (pin "1") (pinfunction "+_1") (pintype "passive"))
      (node (ref "J3") (pin "A4") (pinfunction "VBUS_A4") (pintype "bidirectional"))
      (node (ref "J3") (pin "A9") (pinfunction "VBUS_A9") (pintype "bidirectional"))
      (node (ref "J3") (pin "B4") (pinfunction "VBUS_B4") (pintype "bidirectional"))
      (node (ref "J3") (pin "B9") (pinfunction "VBUS_B9") (pintype "bidirectional"))
      (node (ref "R45") (pin "2") (pinfunction "2_2") (pintype "passive"))
      (node (ref "U26") (pin "4") (pinfunction "VCC_4") (pintype "bidirectional"))
    )
    (net (code "56") (name "/VCOM") (class "Default")
      (node (ref "C37") (pin "2") (pinfunction "2_2") (pintype "passive"))
      (node (ref "C44") (pin "2") (pinfunction "2_2") (pintype "passive"))
      (node (ref "C45") (pin "2") (pinfunction "2_2") (pintype "passive"))
      (node (ref "L2") (pin "2") (pinfunction "P$2_2") (pintype "bidirectional"))
      (node (ref "R25") (pin "1") (pinfunction "1_1") (pintype "passive"))
      (node (ref "R26") (pin "1") (pinfunction "1_1") (pintype "passive"))
      (node (ref "R30") (pin "1") (pinfunction "1_1") (pintype "passive"))
    )
    (net (code "57") (name "/VDD") (class "Default")
      (node (ref "C24") (pin "1") (pinfunction "1_1") (pintype "passive"))
      (node (ref "C25") (pin "1") (pinfunction "1_1") (pintype "passive"))
      (node (ref "R10") (pin "2") (pinfunction "2_2") (pintype "passive"))
      (node (ref "R50") (pin "2") (pinfunction "2_2") (pintype "passive"))
      (node (ref "U11") (pin "6") (pinfunction "VDD_6") (pintype "bidirectional"))
    )
    (net (code "58") (name "/VGH+18V") (class "Default")
      (node (ref "C40") (pin "2") (pinfunction "2_2") (pintype "passive"))
      (node (ref "D2") (pin "-") (pinfunction "-_-") (pintype "passive"))
      (node (ref "J2") (pin "P$10") (pinfunction "VGH_P$10") (pintype "bidirectional"))
      (node (ref "R27") (pin "1") (pinfunction "1_1") (pintype "passive"))
      (node (ref "R7") (pin "2") (pinfunction "2_2") (pintype "passive"))
    )
    (net (code "59") (name "/VGL-8.2V") (class "Default")
      (node (ref "C41") (pin "2") (pinfunction "2_2") (pintype "passive"))
      (node (ref "D4") (pin "+") (pinfunction "+_+") (pintype "passive"))
      (node (ref "J2") (pin "P$9") (pinfunction "VGL_P$9") (pintype "bidirectional"))
      (node (ref "R28") (pin "1") (pinfunction "1_1") (pintype "passive"))
      (node (ref "R6") (pin "2") (pinfunction "2_2") (pintype "passive"))
    )
    (net (code "60") (name "/VIN") (class "Default")
      (node (ref "C23") (pin "2") (pinfunction "2_2") (pintype "passive"))
      (node (ref "C3") (pin "2") (pinfunction "2_2") (pintype "passive"))
      (node (ref "C36") (pin "2") (pinfunction "2_2") (pintype "passive"))
      (node (ref "C42") (pin "2") (pinfunction "2_2") (pintype "passive"))
      (node (ref "C46") (pin "2") (pinfunction "2_2") (pintype "passive"))
      (node (ref "C6") (pin "2") (pinfunction "2_2") (pintype "passive"))
      (node (ref "D3") (pin "2") (pinfunction "-_2") (pintype "passive"))
      (node (ref "D5") (pin "C") (pinfunction "C_C") (pintype "passive"))
      (node (ref "L1") (pin "1") (pinfunction "P$1_1") (pintype "bidirectional"))
      (node (ref "Q3") (pin "2") (pinfunction "S_2") (pintype "bidirectional"))
      (node (ref "Q30") (pin "2") (pinfunction "S_2") (pintype "bidirectional"))
      (node (ref "R172") (pin "1") (pinfunction "1_1") (pintype "passive"))
      (node (ref "R50") (pin "1") (pinfunction "1_1") (pintype "passive"))
      (node (ref "R51") (pin "1") (pinfunction "1_1") (pintype "passive"))
      (node (ref "R52") (pin "1") (pinfunction "1_1") (pintype "passive"))
      (node (ref "U1") (pin "1") (pinfunction "EN_1") (pintype "bidirectional"))
      (node (ref "U1") (pin "4") (pinfunction "VIN_4") (pintype "bidirectional"))
      (node (ref "U3") (pin "4") (pinfunction "VIN_4") (pintype "bidirectional"))
      (node (ref "U5") (pin "5") (pinfunction "VIN_5") (pintype "bidirectional"))
    )
    (net (code "61") (name "/VIN2") (class "Default")
      (node (ref "C18") (pin "2") (pinfunction "2_2") (pintype "passive"))
      (node (ref "C43") (pin "2") (pinfunction "2_2") (pintype "passive"))
      (node (ref "L5") (pin "1") (pinfunction "1_1") (pintype "bidirectional"))
      (node (ref "Q30") (pin "3") (pinfunction "D_3") (pintype "bidirectional"))
      (node (ref "R49") (pin "2") (pinfunction "2_2") (pintype "passive"))
      (node (ref "R53") (pin "2") (pinfunction "2_2") (pintype "passive"))
      (node (ref "U4") (pin "6") (pinfunction "6-VIN_6") (pintype "bidirectional"))
    )
    (net (code "62") (name "GND") (class "Default")
      (node (ref "C1") (pin "1") (pinfunction "1_1") (pintype "passive"))
      (node (ref "C10") (pin "1") (pinfunction "1_1") (pintype "passive"))
      (node (ref "C11") (pin "2") (pinfunction "2_2") (pintype "passive"))
      (node (ref "C12") (pin "1") (pinfunction "1_1") (pintype "passive"))
      (node (ref "C13") (pin "2") (pinfunction "2_2") (pintype "passive"))
      (node (ref "C14") (pin "2") (pinfunction "2_2") (pintype "passive"))
      (node (ref "C15") (pin "1") (pinfunction "1_1") (pintype "passive"))
      (node (ref "C16") (pin "2") (pinfunction "2_2") (pintype "passive"))
      (node (ref "C17") (pin "1") (pinfunction "1_1") (pintype "passive"))
      (node (ref "C18") (pin "1") (pinfunction "1_1") (pintype "passive"))
      (node (ref "C19") (pin "1") (pinfunction "1_1") (pintype "passive"))
      (node (ref "C2") (pin "2") (pinfunction "2_2") (pintype "passive"))
      (node (ref "C20") (pin "2") (pinfunction "2_2") (pintype "passive"))
      (node (ref "C21") (pin "1") (pinfunction "1_1") (pintype "passive"))
      (node (ref "C22") (pin "1") (pinfunction "1_1") (pintype "passive"))
      (node (ref "C23") (pin "1") (pinfunction "1_1") (pintype "passive"))
      (node (ref "C24") (pin "2") (pinfunction "2_2") (pintype "passive"))
      (node (ref "C25") (pin "2") (pinfunction "2_2") (pintype "passive"))
      (node (ref "C26") (pin "2") (pinfunction "2_2") (pintype "passive"))
      (node (ref "C29") (pin "1") (pinfunction "1_1") (pintype "passive"))
      (node (ref "C3") (pin "1") (pinfunction "1_1") (pintype "passive"))
      (node (ref "C30") (pin "1") (pinfunction "1_1") (pintype "passive"))
      (node (ref "C31") (pin "1") (pinfunction "1_1") (pintype "passive"))
      (node (ref "C32") (pin "1") (pinfunction "1_1") (pintype "passive"))
      (node (ref "C33") (pin "2") (pinfunction "2_2") (pintype "passive"))
      (node (ref "C34") (pin "1") (pinfunction "1_1") (pintype "passive"))
      (node (ref "C35") (pin "1") (pinfunction "1_1") (pintype "passive"))
      (node (ref "C36") (pin "1") (pinfunction "1_1") (pintype "passive"))
      (node (ref "C37") (pin "1") (pinfunction "1_1") (pintype "passive"))
      (node (ref "C4") (pin "1") (pinfunction "1_1") (pintype "passive"))
      (node (ref "C40") (pin "1") (pinfunction "1_1") (pintype "passive"))
      (node (ref "C41") (pin "1") (pinfunction "1_1") (pintype "passive"))
      (node (ref "C42") (pin "1") (pinfunction "1_1") (pintype "passive"))
      (node (ref "C43") (pin "1") (pinfunction "1_1") (pintype "passive"))
      (node (ref "C44") (pin "1") (pinfunction "1_1") (pintype "passive"))
      (node (ref "C45") (pin "1") (pinfunction "1_1") (pintype "passive"))
      (node (ref "C46") (pin "1") (pinfunction "1_1") (pintype "passive"))
      (node (ref "C47") (pin "1") (pinfunction "1_1") (pintype "bidirectional"))
      (node (ref "C48") (pin "1") (pinfunction "1_1") (pintype "bidirectional"))
      (node (ref "C49") (pin "1") (pinfunction "1_1") (pintype "bidirectional"))
      (node (ref "C5") (pin "2") (pinfunction "2_2") (pintype "passive"))
      (node (ref "C50") (pin "2") (pinfunction "2_2") (pintype "passive"))
      (node (ref "C51") (pin "2") (pinfunction "2_2") (pintype "passive"))
      (node (ref "C54") (pin "1") (pinfunction "1_1") (pintype "passive"))
      (node (ref "C6") (pin "1") (pinfunction "1_1") (pintype "passive"))
      (node (ref "C7") (pin "1") (pinfunction "1_1") (pintype "passive"))
      (node (ref "C8") (pin "1") (pinfunction "1_1") (pintype "passive"))
      (node (ref "C9") (pin "1") (pinfunction "1_1") (pintype "passive"))
      (node (ref "D2") (pin "+") (pinfunction "+_+") (pintype "passive"))
      (node (ref "D4") (pin "-") (pinfunction "-_-") (pintype "passive"))
      (node (ref "J1") (pin "P$2") (pinfunction "P$2_P$2") (pintype "bidirectional"))
      (node (ref "J1") (pin "P$3") (pinfunction "P$3_P$3") (pintype "bidirectional"))
      (node (ref "J1") (pin "P$4") (pinfunction "P$4_P$4") (pintype "bidirectional"))
      (node (ref "J10") (pin "4") (pinfunction "4_4") (pintype "bidirectional"))
      (node (ref "J10") (pin "SS1") (pinfunction "SS1_SS1") (pintype "bidirectional"))
      (node (ref "J10") (pin "SS2") (pinfunction "SS2_SS2") (pintype "bidirectional"))
      (node (ref "J2") (pin "P$13") (pinfunction "GND2_P$13") (pintype "bidirectional"))
      (node (ref "J2") (pin "P$15") (pinfunction "GND1_P$15") (pintype "bidirectional"))
      (node (ref "J2") (pin "P$16") (pinfunction "R0_P$16") (pintype "bidirectional"))
      (node (ref "J2") (pin "P$17") (pinfunction "R1_P$17") (pintype "bidirectional"))
      (node (ref "J2") (pin "P$18") (pinfunction "R2_P$18") (pintype "bidirectional"))
      (node (ref "J2") (pin "P$24") (pinfunction "G0_P$24") (pintype "bidirectional"))
      (node (ref "J2") (pin "P$25") (pinfunction "G1_P$25") (pintype "bidirectional"))
      (node (ref "J2") (pin "P$3") (pinfunction "GND3_P$3") (pintype "bidirectional"))
      (node (ref "J2") (pin "P$32") (pinfunction "B0_P$32") (pintype "bidirectional"))
      (node (ref "J2") (pin "P$33") (pinfunction "B1_P$33") (pintype "bidirectional"))
      (node (ref "J2") (pin "P$34") (pinfunction "B2_P$34") (pintype "bidirectional"))
      (node (ref "J2") (pin "P$46") (pinfunction "GND_P$46") (pintype "bidirectional"))
      (node (ref "J3") (pin "A1") (pinfunction "GND_A1") (pintype "bidirectional"))
      (node (ref "J3") (pin "A12") (pinfunction "GND_A12") (pintype "bidirectional"))
      (node (ref "J3") (pin "B1") (pinfunction "GND_B1") (pintype "bidirectional"))
      (node (ref "J3") (pin "B12") (pinfunction "GND_B12") (pintype "bidirectional"))
      (node (ref "J3") (pin "P$6") (pinfunction "P$17_P$6") (pintype "bidirectional"))
      (node (ref "J3") (pin "P$7") (pinfunction "P$18_P$7") (pintype "bidirectional"))
      (node (ref "J3") (pin "P$8") (pinfunction "P$19_P$8") (pintype "bidirectional"))
      (node (ref "J3") (pin "P$9") (pinfunction "P$20_P$9") (pintype "bidirectional"))
      (node (ref "J4") (pin "1") (pinfunction "P$1_1") (pintype "bidirectional"))
      (node (ref "J4") (pin "5") (pinfunction "P$5_5") (pintype "bidirectional"))
      (node (ref "J5") (pin "P$3") (pinfunction "P$3_P$3") (pintype "bidirectional"))
      (node (ref "J5") (pin "P$4") (pinfunction "P$4_P$4") (pintype "bidirectional"))
      (node (ref "J6") (pin "4") (pinfunction "4_4") (pintype "bidirectional"))
      (node (ref "J6") (pin "SS1") (pinfunction "SS1_SS1") (pintype "bidirectional"))
      (node (ref "J6") (pin "SS2") (pinfunction "SS2_SS2") (pintype "bidirectional"))
      (node (ref "J7") (pin "4") (pinfunction "4_4") (pintype "bidirectional"))
      (node (ref "J7") (pin "SS1") (pinfunction "SS1_SS1") (pintype "bidirectional"))
      (node (ref "J7") (pin "SS2") (pinfunction "SS2_SS2") (pintype "bidirectional"))
      (node (ref "K1") (pin "1") (pinfunction "1_1") (pintype "passive"))
      (node (ref "K4") (pin "1") (pinfunction "1_1") (pintype "passive"))
      (node (ref "LED1") (pin "-") (pinfunction "-_-") (pintype "passive"))
      (node (ref "P2") (pin "4") (pinfunction "3_4") (pintype "bidirectional"))
      (node (ref "P2") (pin "7") (pinfunction "7_7") (pintype "bidirectional"))
      (node (ref "P2") (pin "8") (pinfunction "8_8") (pintype "bidirectional"))
      (node (ref "P4") (pin "4") (pinfunction "3_4") (pintype "bidirectional"))
      (node (ref "P4") (pin "7") (pinfunction "7_7") (pintype "bidirectional"))
      (node (ref "P4") (pin "8") (pinfunction "8_8") (pintype "bidirectional"))
      (node (ref "Q2") (pin "2") (pinfunction "P$2_2") (pintype "bidirectional"))
      (node (ref "Q5") (pin "2") (pinfunction "E_2") (pintype "passive"))
      (node (ref "Q6") (pin "2") (pinfunction "E_2") (pintype "passive"))
      (node (ref "R13") (pin "1") (pinfunction "1_1") (pintype "passive"))
      (node (ref "R14") (pin "2") (pinfunction "2_2") (pintype "passive"))
      (node (ref "R15") (pin "2") (pinfunction "2_2") (pintype "passive"))
      (node (ref "R2") (pin "2") (pinfunction "2_2") (pintype "passive"))
      (node (ref "R21") (pin "2") (pinfunction "2_2") (pintype "passive"))
      (node (ref "R27") (pin "2") (pinfunction "2_2") (pintype "passive"))
      (node (ref "R28") (pin "2") (pinfunction "2_2") (pintype "passive"))
      (node (ref "R29") (pin "2") (pinfunction "2_2") (pintype "passive"))
      (node (ref "R31") (pin "1") (pinfunction "1_1") (pintype "passive"))
      (node (ref "R33") (pin "1") (pinfunction "1_1") (pintype "passive"))
      (node (ref "R35") (pin "1") (pinfunction "1_1") (pintype "passive"))
      (node (ref "R37") (pin "1") (pinfunction "1_1") (pintype "passive"))
      (node (ref "R43") (pin "2") (pinfunction "2_2") (pintype "passive"))
      (node (ref "R44") (pin "1") (pinfunction "1_1") (pintype "passive"))
      (node (ref "R55") (pin "1") (pinfunction "1_1") (pintype "passive"))
      (node (ref "R58") (pin "1") (pinfunction "1_1") (pintype "passive"))
      (node (ref "SD1") (pin "6") (pinfunction "VSS_6") (pintype "bidirectional"))
      (node (ref "SD1") (pin "G1") (pinfunction "G1_G1") (pintype "bidirectional"))
      (node (ref "SD1") (pin "G2") (pinfunction "G2_G2") (pintype "bidirectional"))
      (node (ref "SD1") (pin "G3") (pinfunction "G3_G3") (pintype "bidirectional"))
      (node (ref "SD1") (pin "G4") (pinfunction "G4_G4") (pintype "bidirectional"))
      (node (ref "U1") (pin "2") (pinfunction "GND_2") (pintype "bidirectional"))
      (node (ref "U11") (pin "7") (pinfunction "GND_7") (pintype "bidirectional"))
      (node (ref "U11") (pin "9") (pinfunction "PE_9") (pintype "bidirectional"))
      (node (ref "U2") (pin "1") (pinfunction "GND1_1") (pintype "bidirectional"))
      (node (ref "U2") (pin "40") (pinfunction "GND2_40") (pintype "bidirectional"))
      (node (ref "U2") (pin "41") (pinfunction "GND3_41") (pintype "bidirectional"))
      (node (ref "U2") (pin "42") (pinfunction "GND4_42") (pintype "bidirectional"))
      (node (ref "U2") (pin "43") (pinfunction "GND5_43") (pintype "bidirectional"))
      (node (ref "U2") (pin "44") (pinfunction "GND6_44") (pintype "bidirectional"))
      (node (ref "U2") (pin "45") (pinfunction "GND7_45") (pintype "bidirectional"))
      (node (ref "U2") (pin "46") (pinfunction "GND8_46") (pintype "bidirectional"))
      (node (ref "U2") (pin "47") (pinfunction "GND9_47") (pintype "bidirectional"))
      (node (ref "U2") (pin "48") (pinfunction "GND10_48") (pintype "bidirectional"))
      (node (ref "U2") (pin "49") (pinfunction "GND11_49") (pintype "bidirectional"))
      (node (ref "U26") (pin "2") (pinfunction "GND_2") (pintype "bidirectional"))
      (node (ref "U3") (pin "2") (pinfunction "GND_2") (pintype "bidirectional"))
      (node (ref "U4") (pin "2") (pinfunction "2-GND_2") (pintype "bidirectional"))
      (node (ref "U5") (pin "2") (pinfunction "GND_2") (pintype "bidirectional"))
      (node (ref "U6") (pin "1") (pinfunction "GND_1") (pintype "bidirectional"))
    )
    (net (code "63") (name "Net-(C14-Pad1)") (class "Default")
      (node (ref "C14") (pin "1") (pinfunction "1_1") (pintype "passive"))
      (node (ref "C38") (pin "1") (pinfunction "1_1") (pintype "passive"))
      (node (ref "J5") (pin "P$2") (pinfunction "P$2_P$2") (pintype "bidirectional"))
    )
    (net (code "64") (name "Net-(C16-Pad1)") (class "Default")
      (node (ref "C16") (pin "1") (pinfunction "1_1") (pintype "passive"))
      (node (ref "C39") (pin "1") (pinfunction "1_1") (pintype "passive"))
      (node (ref "J5") (pin "P$1") (pinfunction "P$1_P$1") (pintype "bidirectional"))
    )
    (net (code "65") (name "Net-(D1-+)") (class "Default")
      (node (ref "C27") (pin "2") (pinfunction "2_2") (pintype "passive"))
      (node (ref "C28") (pin "2") (pinfunction "2_2") (pintype "passive"))
      (node (ref "D1") (pin "1") (pinfunction "+_1") (pintype "passive"))
      (node (ref "L1") (pin "2") (pinfunction "P$2_2") (pintype "bidirectional"))
      (node (ref "U5") (pin "1") (pinfunction "LX_1") (pintype "bidirectional"))
    )
    (net (code "66") (name "Net-(D6-+)") (class "Default")
      (node (ref "D6") (pin "1") (pinfunction "+_1") (pintype "passive"))
      (node (ref "L5") (pin "2") (pinfunction "2_2") (pintype "bidirectional"))
      (node (ref "U4") (pin "1") (pinfunction "1-SW_1") (pintype "bidirectional"))
    )
    (net (code "67") (name "Net-(J2-DCLK)") (class "Default")
      (node (ref "C1") (pin "2") (pinfunction "2_2") (pintype "passive"))
      (node (ref "J2") (pin "P$14") (pinfunction "DCLK_P$14") (pintype "bidirectional"))
      (node (ref "R38") (pin "2") (pinfunction "2_2") (pintype "passive"))
    )
    (net (code "68") (name "Net-(J2-DITHB)") (class "Default")
      (node (ref "J2") (pin "P$4") (pinfunction "DITHB_P$4") (pintype "bidirectional"))
      (node (ref "R39") (pin "1") (pinfunction "1_1") (pintype "passive"))
    )
    (net (code "69") (name "Net-(J2-MODE)") (class "Default")
      (node (ref "J2") (pin "P$43") (pinfunction "MODE_P$43") (pintype "bidirectional"))
      (node (ref "R36") (pin "1") (pinfunction "1_1") (pintype "passive"))
      (node (ref "R37") (pin "2") (pinfunction "2_2") (pintype "passive"))
    )
    (net (code "70") (name "Net-(J2-VCOM)") (class "Default")
      (node (ref "J2") (pin "P$45") (pinfunction "VCOM_P$45") (pintype "bidirectional"))
      (node (ref "R25") (pin "2") (pinfunction "2_2") (pintype "passive"))
    )
    (net (code "71") (name "Net-(J2-VCOM1)") (class "Default")
      (node (ref "J2") (pin "P$5") (pinfunction "VCOM1_P$5") (pintype "bidirectional"))
      (node (ref "R26") (pin "2") (pinfunction "2_2") (pintype "passive"))
    )
    (net (code "72") (name "Net-(J3-CC1)") (class "Default")
      (node (ref "J3") (pin "A5") (pinfunction "CC1_A5") (pintype "bidirectional"))
      (node (ref "R13") (pin "2") (pinfunction "2_2") (pintype "passive"))
    )
    (net (code "73") (name "Net-(J3-CC2)") (class "Default")
      (node (ref "J3") (pin "B5") (pinfunction "CC2_B5") (pintype "bidirectional"))
      (node (ref "R14") (pin "1") (pinfunction "1_1") (pintype "passive"))
    )
    (net (code "74") (name "Net-(L2-P$1)") (class "Default")
      (node (ref "L2") (pin "1") (pinfunction "P$1_1") (pintype "bidirectional"))
      (node (ref "U3") (pin "3") (pinfunction "SW_3") (pintype "bidirectional"))
    )
    (net (code "75") (name "Net-(L4-P$1)") (class "Default")
      (node (ref "L4") (pin "1") (pinfunction "P$1_1") (pintype "bidirectional"))
      (node (ref "U1") (pin "3") (pinfunction "SW_3") (pintype "bidirectional"))
    )
    (net (code "76") (name "Net-(LED1-Pad+)") (class "Default")
      (node (ref "LED1") (pin "+") (pinfunction "+_+") (pintype "passive"))
      (node (ref "R3") (pin "1") (pinfunction "1_1") (pintype "passive"))
    )
    (net (code "77") (name "Net-(Q1-P$2)") (class "Default")
      (node (ref "C35") (pin "2") (pinfunction "2_2") (pintype "passive"))
      (node (ref "Q1") (pin "2") (pinfunction "P$2_2") (pintype "bidirectional"))
      (node (ref "R7") (pin "1") (pinfunction "1_1") (pintype "passive"))
    )
    (net (code "78") (name "Net-(Q1-P$3)") (class "Default")
      (node (ref "C27") (pin "1") (pinfunction "1_1") (pintype "passive"))
      (node (ref "Q1") (pin "3") (pinfunction "P$3_3") (pintype "bidirectional"))
    )
    (net (code "79") (name "Net-(Q2-P$1)") (class "Default")
      (node (ref "C34") (pin "2") (pinfunction "2_2") (pintype "passive"))
      (node (ref "Q2") (pin "1") (pinfunction "P$1_1") (pintype "bidirectional"))
      (node (ref "R6") (pin "1") (pinfunction "1_1") (pintype "passive"))
    )
    (net (code "80") (name "Net-(Q2-P$3)") (class "Default")
      (node (ref "C28") (pin "1") (pinfunction "1_1") (pintype "passive"))
      (node (ref "Q2") (pin "3") (pinfunction "P$3_3") (pintype "bidirectional"))
    )
    (net (code "81") (name "Net-(Q3-G)") (class "Default")
      (node (ref "Q3") (pin "1") (pinfunction "G_1") (pintype "bidirectional"))
      (node (ref "R44") (pin "2") (pinfunction "2_2") (pintype "passive"))
      (node (ref "R45") (pin "1") (pinfunction "1_1") (pintype "passive"))
    )
    (net (code "82") (name "Net-(Q4-G)") (class "Default")
      (node (ref "Q4") (pin "1") (pinfunction "G_1") (pintype "bidirectional"))
      (node (ref "Q6") (pin "3") (pinfunction "C_3") (pintype "passive"))
      (node (ref "R48") (pin "2") (pinfunction "2_2") (pintype "passive"))
    )
    (net (code "83") (name "Net-(Q5-B)") (class "Default")
      (node (ref "Q5") (pin "1") (pinfunction "B_1") (pintype "passive"))
      (node (ref "R11") (pin "1") (pinfunction "1_1") (pintype "passive"))
      (node (ref "R58") (pin "2") (pinfunction "2_2") (pintype "passive"))
    )
    (net (code "84") (name "Net-(Q6-B)") (class "Default")
      (node (ref "Q6") (pin "1") (pinfunction "B_1") (pintype "passive"))
      (node (ref "R54") (pin "1") (pinfunction "1_1") (pintype "passive"))
      (node (ref "R55") (pin "2") (pinfunction "2_2") (pintype "passive"))
    )
    (net (code "85") (name "Net-(Q9-B)") (class "Default")
      (node (ref "Q9") (pin "1") (pinfunction "B_1") (pintype "passive"))
      (node (ref "R75") (pin "1") (pinfunction "1_1") (pintype "passive"))
    )
    (net (code "86") (name "Net-(Q10-B)") (class "Default")
      (node (ref "Q10") (pin "1") (pinfunction "B_1") (pintype "passive"))
      (node (ref "R74") (pin "1") (pinfunction "1_1") (pintype "passive"))
    )
    (net (code "87") (name "Net-(Q30-G)") (class "Default")
      (node (ref "Q30") (pin "1") (pinfunction "G_1") (pintype "bidirectional"))
      (node (ref "Q5") (pin "3") (pinfunction "C_3") (pintype "passive"))
      (node (ref "R172") (pin "2") (pinfunction "2_2") (pintype "passive"))
    )
    (net (code "88") (name "Net-(SD1-DATA1)") (class "Default")
      (node (ref "R17") (pin "2") (pinfunction "2_2") (pintype "passive"))
      (node (ref "SD1") (pin "8") (pinfunction "DATA1_8") (pintype "bidirectional"))
    )
    (net (code "89") (name "Net-(SD1-DATA2)") (class "Default")
      (node (ref "R16") (pin "2") (pinfunction "2_2") (pintype "passive"))
      (node (ref "SD1") (pin "1") (pinfunction "DATA2_1") (pintype "bidirectional"))
    )
    (net (code "90") (name "Net-(U1-FB)") (class "Default")
      (node (ref "R20") (pin "2") (pinfunction "2_2") (pintype "passive"))
      (node (ref "R21") (pin "1") (pinfunction "1_1") (pintype "passive"))
      (node (ref "U1") (pin "5") (pinfunction "FB_5") (pintype "bidirectional"))
    )
    (net (code "91") (name "Net-(U3-EN)") (class "Default")
      (node (ref "R49") (pin "1") (pinfunction "1_1") (pintype "passive"))
      (node (ref "R51") (pin "2") (pinfunction "2_2") (pintype "passive"))
      (node (ref "U3") (pin "1") (pinfunction "EN_1") (pintype "bidirectional"))
    )
    (net (code "92") (name "Net-(U3-FB)") (class "Default")
      (node (ref "R30") (pin "2") (pinfunction "2_2") (pintype "passive"))
      (node (ref "R43") (pin "1") (pinfunction "1_1") (pintype "passive"))
      (node (ref "U3") (pin "5") (pinfunction "FB_5") (pintype "bidirectional"))
    )
    (net (code "93") (name "Net-(U5-EN)") (class "Default")
      (node (ref "R52") (pin "2") (pinfunction "2_2") (pintype "passive"))
      (node (ref "R53") (pin "1") (pinfunction "1_1") (pintype "passive"))
      (node (ref "U5") (pin "4") (pinfunction "EN_4") (pintype "bidirectional"))
    )
    (net (code "94") (name "Net-(U5-FB)") (class "Default")
      (node (ref "R1") (pin "2") (pinfunction "2_2") (pintype "passive"))
      (node (ref "R2") (pin "1") (pinfunction "1_1") (pintype "passive"))
      (node (ref "U5") (pin "3") (pinfunction "FB_3") (pintype "bidirectional"))
    )
    (net (code "95") (name "Net-(U6-RXD)") (class "Default")
      (node (ref "R71") (pin "2") (pinfunction "2_2") (pintype "passive"))
      (node (ref "U6") (pin "3") (pinfunction "RXD_3") (pintype "bidirectional"))
    )
    (net (code "96") (name "Net-(U6-TXD)") (class "Default")
      (node (ref "R72") (pin "2") (pinfunction "2_2") (pintype "passive"))
      (node (ref "U6") (pin "2") (pinfunction "TXD_2") (pintype "bidirectional"))
    )
    (net (code "97") (name "Net-(U11-VON)") (class "Default")
      (node (ref "C39") (pin "2") (pinfunction "2_2") (pintype "passive"))
      (node (ref "U11") (pin "5") (pinfunction "VON_5") (pintype "bidirectional"))
    )
    (net (code "98") (name "Net-(U11-VOP)") (class "Default")
      (node (ref "C38") (pin "2") (pinfunction "2_2") (pintype "passive"))
      (node (ref "U11") (pin "8") (pinfunction "VOP_8") (pintype "bidirectional"))
    )
    (net (code "99") (name "Net-(U26-PROG)") (class "Default")
      (node (ref "R15") (pin "1") (pinfunction "1_1") (pintype "passive"))
      (node (ref "U26") (pin "5") (pinfunction "PROG_5") (pintype "bidirectional"))
    )
    (net (code "100") (name "unconnected-(J2-GND4-PadP$51)") (class "Default")
      (node (ref "J2") (pin "P$51") (pinfunction "GND4_P$51") (pintype "bidirectional"))
    )
    (net (code "101") (name "unconnected-(J2-GND5-PadP$52)") (class "Default")
      (node (ref "J2") (pin "P$52") (pinfunction "GND5_P$52") (pintype "bidirectional"))
    )
    (net (code "102") (name "unconnected-(J2-NC-PadP$6)") (class "Default")
      (node (ref "J2") (pin "P$6") (pinfunction "NC_P$6") (pintype "bidirectional"))
    )
    (net (code "103") (name "unconnected-(J2-NC1-PadP$2)") (class "Default")
      (node (ref "J2") (pin "P$2") (pinfunction "NC1_P$2") (pintype "bidirectional"))
    )
    (net (code "104") (name "unconnected-(J2-NC2-PadP$1)") (class "Default")
      (node (ref "J2") (pin "P$1") (pinfunction "NC2_P$1") (pintype "bidirectional"))
    )
    (net (code "105") (name "unconnected-(J3-SBU1-PadA8)") (class "Default")
      (node (ref "J3") (pin "A8") (pinfunction "SBU1_A8") (pintype "bidirectional"))
    )
    (net (code "106") (name "unconnected-(J3-SBU2-PadB8)") (class "Default")
      (node (ref "J3") (pin "B8") (pinfunction "SBU2_B8") (pintype "bidirectional"))
    )
    (net (code "107") (name "unconnected-(J4-P$3-Pad3)") (class "Default")
      (node (ref "J4") (pin "3") (pinfunction "P$3_3") (pintype "bidirectional"))
    )
    (net (code "108") (name "unconnected-(J7-Pad2)") (class "Default")
      (node (ref "J7") (pin "2") (pinfunction "2_2") (pintype "bidirectional"))
    )
    (net (code "109") (name "unconnected-(SD1-CDN-Pad9)") (class "Default")
      (node (ref "SD1") (pin "9") (pinfunction "CDN_9") (pintype "bidirectional"))
    )
    (net (code "110") (name "unconnected-(U2-NC1-Pad28)") (class "Default")
      (node (ref "U2") (pin "28") (pinfunction "NC1_28") (pintype "bidirectional"))
    )
    (net (code "111") (name "unconnected-(U2-NC2-Pad29)") (class "Default")
      (node (ref "U2") (pin "29") (pinfunction "NC2_29") (pintype "bidirectional"))
    )
    (net (code "112") (name "unconnected-(U2-NC3-Pad30)") (class "Default")
      (node (ref "U2") (pin "30") (pinfunction "NC3_30") (pintype "bidirectional"))
    )
    (net (code "113") (name "unconnected-(U6-CTS#-Pad9)") (class "Default")
      (node (ref "U6") (pin "9") (pinfunction "CTS#_9") (pintype "bidirectional"))
    )
    (net (code "114") (name "unconnected-(U6-DCD#-Pad12)") (class "Default")
      (node (ref "U6") (pin "12") (pinfunction "DCD#_12") (pintype "bidirectional"))
    )
    (net (code "115") (name "unconnected-(U6-DSR#-Pad10)") (class "Default")
      (node (ref "U6") (pin "10") (pinfunction "DSR#_10") (pintype "bidirectional"))
    )
    (net (code "116") (name "unconnected-(U6-RI#-Pad11)") (class "Default")
      (node (ref "U6") (pin "11") (pinfunction "RI#_11") (pintype "bidirectional"))
    )
    (net (code "117") (name "unconnected-(U6-RS232-Pad15)") (class "Default")
      (node (ref "U6") (pin "15") (pinfunction "RS232_15") (pintype "bidirectional"))
    )
    (net (code "118") (name "unconnected-(U6-XI-Pad7)") (class "Default")
      (node (ref "U6") (pin "7") (pinfunction "XI_7") (pintype "bidirectional"))
    )
    (net (code "119") (name "unconnected-(U6-XO-Pad8)") (class "Default")
      (node (ref "U6") (pin "8") (pinfunction "XO_8") (pintype "bidirectional"))
    )
    (net (code "120") (name "unconnected-(U26-GHRG-Pad1)") (class "Default")
      (node (ref "U26") (pin "1") (pinfunction "GHRG_1") (pintype "bidirectional"))
    )
  )
)
